# CLKB_clocking_system.net
KiCad netlist of a schematic drawn in Altium Designer
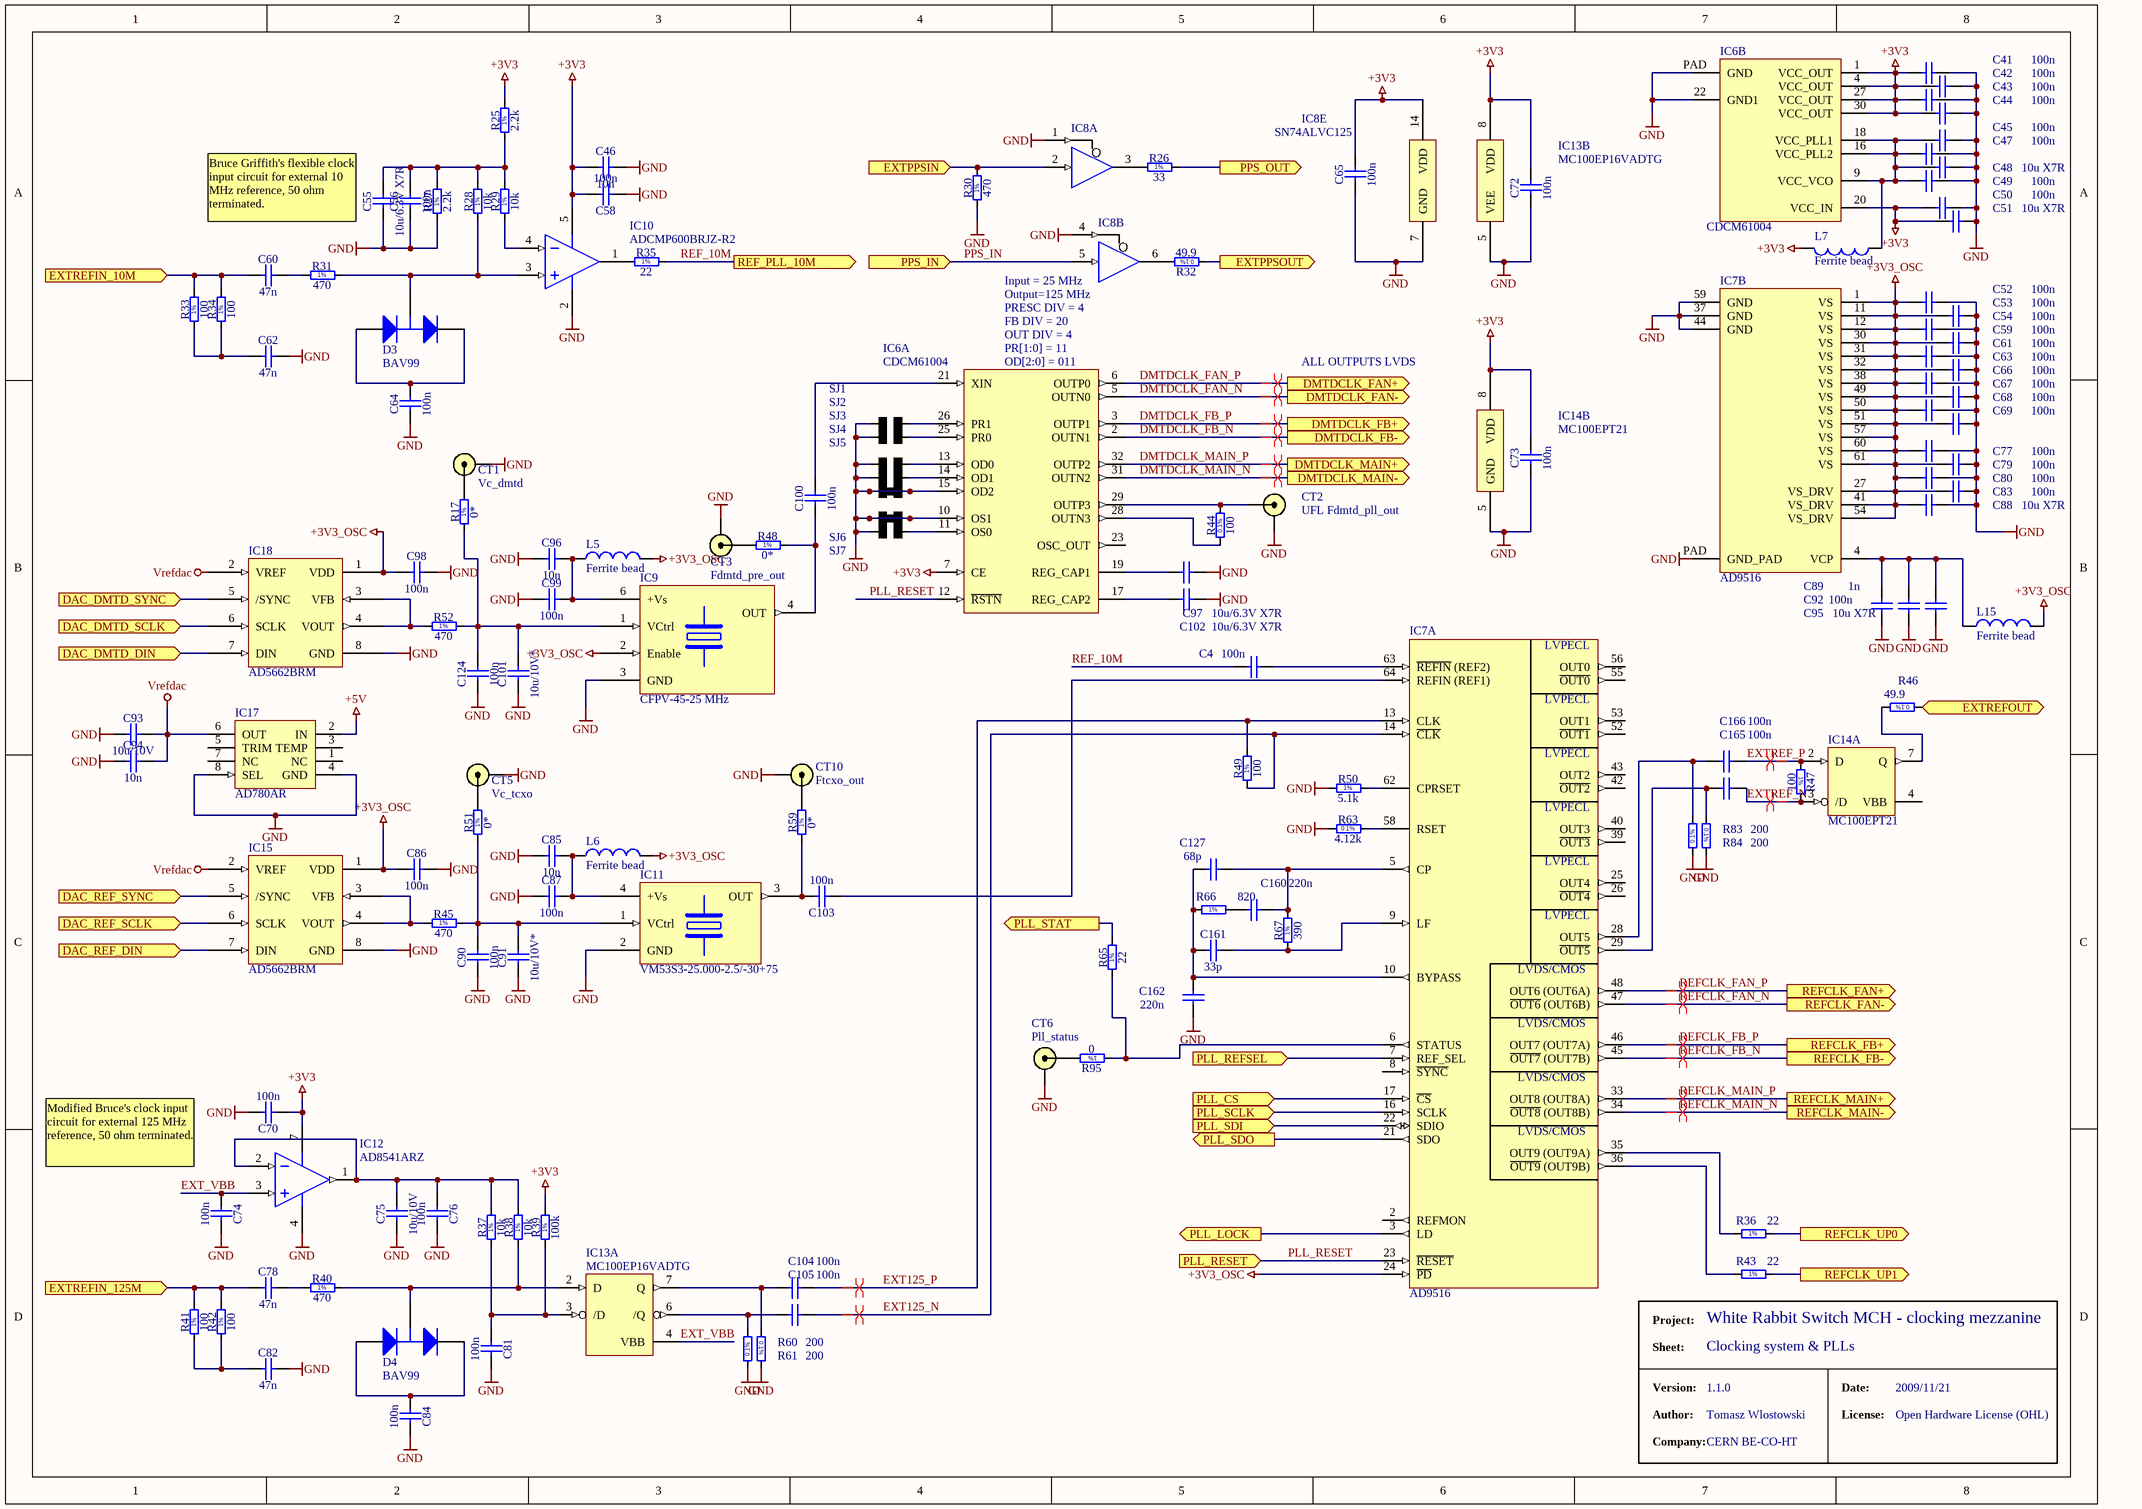
[diagram p0: CLKB_clocking_system.SchDoc]

(export (version "E")
  (design (tool "Eeschema 10.0.6"))
  (components
    (comp (ref "C4")
      (value "100n")
      (footprint "CAPC1608X87N")
      (description "Non-polarised capacitor")
      (fields
        (field (name "PART NUMBER") "CC0603_100NF_50V_10%_X7R")
        (field (name "VOLTAGE") "50V")
        (field (name "AUTHOR") "CERN DEM JLC")
      )
      (libsource (lib "Capacitors") (part "Capacitor - non polarized"))
    )
    (comp (ref "C41")
      (value "100n")
      (footprint "CAPC1005X55N")
      (description "Non-polarised capacitor")
      (fields
        (field (name "PART NUMBER") "CC0402_100NF_16V_10%_X7R")
        (field (name "VOLTAGE") "16V")
        (field (name "AUTHOR") "CERN DEM JLC")
      )
      (libsource (lib "Capacitors") (part "Capacitor - non polarized"))
    )
    (comp (ref "C42")
      (value "100n")
      (footprint "CAPC1005X55N")
      (description "Non-polarised capacitor")
      (fields
        (field (name "PART NUMBER") "CC0402_100NF_16V_10%_X7R")
        (field (name "VOLTAGE") "16V")
        (field (name "AUTHOR") "CERN DEM JLC")
      )
      (libsource (lib "Capacitors") (part "Capacitor - non polarized"))
    )
    (comp (ref "C43")
      (value "100n")
      (footprint "CAPC1005X55N")
      (description "Non-polarised capacitor")
      (fields
        (field (name "PART NUMBER") "CC0402_100NF_16V_10%_X7R")
        (field (name "VOLTAGE") "16V")
        (field (name "AUTHOR") "CERN DEM JLC")
      )
      (libsource (lib "Capacitors") (part "Capacitor - non polarized"))
    )
    (comp (ref "C44")
      (value "100n")
      (footprint "CAPC1005X55N")
      (description "Non-polarised capacitor")
      (fields
        (field (name "PART NUMBER") "CC0402_100NF_16V_10%_X7R")
        (field (name "VOLTAGE") "16V")
        (field (name "AUTHOR") "CERN DEM JLC")
      )
      (libsource (lib "Capacitors") (part "Capacitor - non polarized"))
    )
    (comp (ref "C45")
      (value "100n")
      (footprint "CAPC1005X55N")
      (description "Non-polarised capacitor")
      (fields
        (field (name "PART NUMBER") "CC0402_100NF_16V_10%_X7R")
        (field (name "VOLTAGE") "16V")
        (field (name "AUTHOR") "CERN DEM JLC")
      )
      (libsource (lib "Capacitors") (part "Capacitor - non polarized"))
    )
    (comp (ref "C46")
      (value "10n")
      (footprint "CAPC1608X87N")
      (description "Non-polarised capacitor")
      (fields
        (field (name "PART NUMBER") "CC0603_10NF_50V_10%_X7R")
        (field (name "VOLTAGE") "50V")
        (field (name "AUTHOR") "CERN DEM JLC")
      )
      (libsource (lib "Capacitors") (part "Capacitor - non polarized"))
    )
    (comp (ref "C47")
      (value "100n")
      (footprint "CAPC1005X55N")
      (description "Non-polarised capacitor")
      (fields
        (field (name "PART NUMBER") "CC0402_100NF_16V_10%_X7R")
        (field (name "VOLTAGE") "16V")
        (field (name "AUTHOR") "CERN DEM JLC")
      )
      (libsource (lib "Capacitors") (part "Capacitor - non polarized"))
    )
    (comp (ref "C48")
      (value "10u X7R")
      (footprint "CAPC1608X87N")
      (description "Non-polarised capacitor")
      (fields
        (field (name "PART NUMBER") "CC0603_10UF_6.3V_20%_X5R")
        (field (name "VOLTAGE") "6.3V")
        (field (name "AUTHOR") "CERN DEM JLC")
      )
      (libsource (lib "Capacitors") (part "Capacitor - non polarized"))
    )
    (comp (ref "C49")
      (value "100n")
      (footprint "CAPC1005X55N")
      (description "Non-polarised capacitor")
      (fields
        (field (name "PART NUMBER") "CC0402_100NF_16V_10%_X7R")
        (field (name "VOLTAGE") "16V")
        (field (name "AUTHOR") "CERN DEM JLC")
      )
      (libsource (lib "Capacitors") (part "Capacitor - non polarized"))
    )
    (comp (ref "C50")
      (value "100n")
      (footprint "CAPC1005X55N")
      (description "Non-polarised capacitor")
      (fields
        (field (name "PART NUMBER") "CC0402_100NF_16V_10%_X7R")
        (field (name "VOLTAGE") "16V")
        (field (name "AUTHOR") "CERN DEM JLC")
      )
      (libsource (lib "Capacitors") (part "Capacitor - non polarized"))
    )
    (comp (ref "C51")
      (value "10u X7R")
      (footprint "CAPC1608X87N")
      (description "Non-polarised capacitor")
      (fields
        (field (name "PART NUMBER") "CC0603_10UF_6.3V_20%_X5R")
        (field (name "VOLTAGE") "6.3V")
        (field (name "AUTHOR") "CERN DEM JLC")
      )
      (libsource (lib "Capacitors") (part "Capacitor - non polarized"))
    )
    (comp (ref "C52")
      (value "100n")
      (footprint "CAPC1005X55N")
      (description "Non-polarised capacitor")
      (fields
        (field (name "PART NUMBER") "CC0402_100NF_16V_10%_X7R")
        (field (name "VOLTAGE") "16V")
        (field (name "AUTHOR") "CERN DEM JLC")
      )
      (libsource (lib "Capacitors") (part "Capacitor - non polarized"))
    )
    (comp (ref "C53")
      (value "100n")
      (footprint "CAPC1005X55N")
      (description "Non-polarised capacitor")
      (fields
        (field (name "PART NUMBER") "CC0402_100NF_16V_10%_X7R")
        (field (name "VOLTAGE") "16V")
        (field (name "AUTHOR") "CERN DEM JLC")
      )
      (libsource (lib "Capacitors") (part "Capacitor - non polarized"))
    )
    (comp (ref "C54")
      (value "100n")
      (footprint "CAPC1005X55N")
      (description "Non-polarised capacitor")
      (fields
        (field (name "PART NUMBER") "CC0402_100NF_16V_10%_X7R")
        (field (name "VOLTAGE") "16V")
        (field (name "AUTHOR") "CERN DEM JLC")
      )
      (libsource (lib "Capacitors") (part "Capacitor - non polarized"))
    )
    (comp (ref "C55")
      (value "10u/6.3V X7R")
      (footprint "CAPC3216X140N")
      (description "Non-polarised capacitor")
      (fields
        (field (name "PART NUMBER") "CC1206_10UF_10V_10%_X7R")
        (field (name "VOLTAGE") "10V")
        (field (name "AUTHOR") "CERN DEM JLC")
      )
      (libsource (lib "Capacitors") (part "Capacitor - non polarized"))
    )
    (comp (ref "C56")
      (value "100n")
      (footprint "CAPC1608X87N")
      (description "Non-polarised capacitor")
      (fields
        (field (name "PART NUMBER") "CC0603_100NF_50V_10%_X7R")
        (field (name "VOLTAGE") "50V")
        (field (name "AUTHOR") "CERN DEM JLC")
      )
      (libsource (lib "Capacitors") (part "Capacitor - non polarized"))
    )
    (comp (ref "C58")
      (value "100n")
      (footprint "CAPC1608X87N")
      (description "Non-polarised capacitor")
      (fields
        (field (name "PART NUMBER") "CC0603_100NF_50V_10%_X7R")
        (field (name "VOLTAGE") "50V")
        (field (name "AUTHOR") "CERN DEM JLC")
      )
      (libsource (lib "Capacitors") (part "Capacitor - non polarized"))
    )
    (comp (ref "C59")
      (value "100n")
      (footprint "CAPC1005X55N")
      (description "Non-polarised capacitor")
      (fields
        (field (name "PART NUMBER") "CC0402_100NF_16V_10%_X7R")
        (field (name "VOLTAGE") "16V")
        (field (name "AUTHOR") "CERN DEM JLC")
      )
      (libsource (lib "Capacitors") (part "Capacitor - non polarized"))
    )
    (comp (ref "C60")
      (value "47n")
      (footprint "CAPC1608X87N")
      (description "Non-polarised capacitor")
      (fields
        (field (name "PART NUMBER") "CC0603_47NF_25V_10%_X7R")
        (field (name "VOLTAGE") "25V")
        (field (name "AUTHOR") "CERN DEM JLC")
      )
      (libsource (lib "Capacitors") (part "Capacitor - non polarized"))
    )
    (comp (ref "C61")
      (value "100n")
      (footprint "CAPC1005X55N")
      (description "Non-polarised capacitor")
      (fields
        (field (name "PART NUMBER") "CC0402_100NF_16V_10%_X7R")
        (field (name "VOLTAGE") "16V")
        (field (name "AUTHOR") "CERN DEM JLC")
      )
      (libsource (lib "Capacitors") (part "Capacitor - non polarized"))
    )
    (comp (ref "C62")
      (value "47n")
      (footprint "CAPC1608X87N")
      (description "Non-polarised capacitor")
      (fields
        (field (name "PART NUMBER") "CC0603_47NF_25V_10%_X7R")
        (field (name "VOLTAGE") "25V")
        (field (name "AUTHOR") "CERN DEM JLC")
      )
      (libsource (lib "Capacitors") (part "Capacitor - non polarized"))
    )
    (comp (ref "C63")
      (value "100n")
      (footprint "CAPC1005X55N")
      (description "Non-polarised capacitor")
      (fields
        (field (name "PART NUMBER") "CC0402_100NF_16V_10%_X7R")
        (field (name "VOLTAGE") "16V")
        (field (name "AUTHOR") "CERN DEM JLC")
      )
      (libsource (lib "Capacitors") (part "Capacitor - non polarized"))
    )
    (comp (ref "C64")
      (value "100n")
      (footprint "CAPC1608X87N")
      (description "Non-polarised capacitor")
      (fields
        (field (name "PART NUMBER") "CC0603_100NF_50V_10%_X7R")
        (field (name "VOLTAGE") "50V")
        (field (name "AUTHOR") "CERN DEM JLC")
      )
      (libsource (lib "Capacitors") (part "Capacitor - non polarized"))
    )
    (comp (ref "C65")
      (value "100n")
      (footprint "CAPC1608X87N")
      (description "Non-polarised capacitor")
      (fields
        (field (name "PART NUMBER") "CC0603_100NF_50V_10%_X7R")
        (field (name "VOLTAGE") "50V")
        (field (name "AUTHOR") "CERN DEM JLC")
      )
      (libsource (lib "Capacitors") (part "Capacitor - non polarized"))
    )
    (comp (ref "C66")
      (value "100n")
      (footprint "CAPC1005X55N")
      (description "Non-polarised capacitor")
      (fields
        (field (name "PART NUMBER") "CC0402_100NF_16V_10%_X7R")
        (field (name "VOLTAGE") "16V")
        (field (name "AUTHOR") "CERN DEM JLC")
      )
      (libsource (lib "Capacitors") (part "Capacitor - non polarized"))
    )
    (comp (ref "C67")
      (value "100n")
      (footprint "CAPC1005X55N")
      (description "Non-polarised capacitor")
      (fields
        (field (name "PART NUMBER") "CC0402_100NF_16V_10%_X7R")
        (field (name "VOLTAGE") "16V")
        (field (name "AUTHOR") "CERN DEM JLC")
      )
      (libsource (lib "Capacitors") (part "Capacitor - non polarized"))
    )
    (comp (ref "C68")
      (value "100n")
      (footprint "CAPC1005X55N")
      (description "Non-polarised capacitor")
      (fields
        (field (name "PART NUMBER") "CC0402_100NF_16V_10%_X7R")
        (field (name "VOLTAGE") "16V")
        (field (name "AUTHOR") "CERN DEM JLC")
      )
      (libsource (lib "Capacitors") (part "Capacitor - non polarized"))
    )
    (comp (ref "C69")
      (value "100n")
      (footprint "CAPC1005X55N")
      (description "Non-polarised capacitor")
      (fields
        (field (name "PART NUMBER") "CC0402_100NF_16V_10%_X7R")
        (field (name "VOLTAGE") "16V")
        (field (name "AUTHOR") "CERN DEM JLC")
      )
      (libsource (lib "Capacitors") (part "Capacitor - non polarized"))
    )
    (comp (ref "C70")
      (value "100n")
      (footprint "CAPC1608X87N")
      (description "Non-polarised capacitor")
      (fields
        (field (name "PART NUMBER") "CC0603_100NF_50V_10%_X7R")
        (field (name "VOLTAGE") "50V")
        (field (name "AUTHOR") "CERN DEM JLC")
      )
      (libsource (lib "Capacitors") (part "Capacitor - non polarized"))
    )
    (comp (ref "C72")
      (value "100n")
      (footprint "CAPC1608X87N")
      (description "Non-polarised capacitor")
      (fields
        (field (name "PART NUMBER") "CC0603_100NF_50V_10%_X7R")
        (field (name "VOLTAGE") "50V")
        (field (name "AUTHOR") "CERN DEM JLC")
      )
      (libsource (lib "Capacitors") (part "Capacitor - non polarized"))
    )
    (comp (ref "C73")
      (value "100n")
      (footprint "CAPC1608X87N")
      (description "Non-polarised capacitor")
      (fields
        (field (name "PART NUMBER") "CC0603_100NF_50V_10%_X7R")
        (field (name "VOLTAGE") "50V")
        (field (name "AUTHOR") "CERN DEM JLC")
      )
      (libsource (lib "Capacitors") (part "Capacitor - non polarized"))
    )
    (comp (ref "C74")
      (value "100n")
      (footprint "CAPC1608X87N")
      (description "Non-polarised capacitor")
      (fields
        (field (name "PART NUMBER") "CC0603_100NF_50V_10%_X7R")
        (field (name "VOLTAGE") "50V")
        (field (name "AUTHOR") "CERN DEM JLC")
      )
      (libsource (lib "Capacitors") (part "Capacitor - non polarized"))
    )
    (comp (ref "C75")
      (value "10u/10V")
      (footprint "CAPC3216X140N")
      (description "Non-polarised capacitor")
      (fields
        (field (name "PART NUMBER") "CC1206_10UF_10V_10%_X7R")
        (field (name "VOLTAGE") "10V")
        (field (name "AUTHOR") "CERN DEM JLC")
      )
      (libsource (lib "Capacitors") (part "Capacitor - non polarized"))
    )
    (comp (ref "C76")
      (value "100n")
      (footprint "CAPC1608X87N")
      (description "Non-polarised capacitor")
      (fields
        (field (name "PART NUMBER") "CC0603_100NF_50V_10%_X7R")
        (field (name "VOLTAGE") "50V")
        (field (name "AUTHOR") "CERN DEM JLC")
      )
      (libsource (lib "Capacitors") (part "Capacitor - non polarized"))
    )
    (comp (ref "C77")
      (value "100n")
      (footprint "CAPC1005X55N")
      (description "Non-polarised capacitor")
      (fields
        (field (name "PART NUMBER") "CC0402_100NF_16V_10%_X7R")
        (field (name "VOLTAGE") "16V")
        (field (name "AUTHOR") "CERN DEM JLC")
      )
      (libsource (lib "Capacitors") (part "Capacitor - non polarized"))
    )
    (comp (ref "C78")
      (value "47n")
      (footprint "CAPC1608X87N")
      (description "Non-polarised capacitor")
      (fields
        (field (name "PART NUMBER") "CC0603_47NF_25V_10%_X7R")
        (field (name "VOLTAGE") "25V")
        (field (name "AUTHOR") "CERN DEM JLC")
      )
      (libsource (lib "Capacitors") (part "Capacitor - non polarized"))
    )
    (comp (ref "C79")
      (value "100n")
      (footprint "CAPC1005X55N")
      (description "Non-polarised capacitor")
      (fields
        (field (name "PART NUMBER") "CC0402_100NF_16V_10%_X7R")
        (field (name "VOLTAGE") "16V")
        (field (name "AUTHOR") "CERN DEM JLC")
      )
      (libsource (lib "Capacitors") (part "Capacitor - non polarized"))
    )
    (comp (ref "C80")
      (value "100n")
      (footprint "CAPC1005X55N")
      (description "Non-polarised capacitor")
      (fields
        (field (name "PART NUMBER") "CC0402_100NF_16V_10%_X7R")
        (field (name "VOLTAGE") "16V")
        (field (name "AUTHOR") "CERN DEM JLC")
      )
      (libsource (lib "Capacitors") (part "Capacitor - non polarized"))
    )
    (comp (ref "C81")
      (value "100n")
      (footprint "CAPC1608X87N")
      (description "Non-polarised capacitor")
      (fields
        (field (name "PART NUMBER") "CC0603_100NF_50V_10%_X7R")
        (field (name "VOLTAGE") "50V")
        (field (name "AUTHOR") "CERN DEM JLC")
      )
      (libsource (lib "Capacitors") (part "Capacitor - non polarized"))
    )
    (comp (ref "C82")
      (value "47n")
      (footprint "CAPC1608X87N")
      (description "Non-polarised capacitor")
      (fields
        (field (name "PART NUMBER") "CC0603_47NF_25V_10%_X7R")
        (field (name "VOLTAGE") "25V")
        (field (name "AUTHOR") "CERN DEM JLC")
      )
      (libsource (lib "Capacitors") (part "Capacitor - non polarized"))
    )
    (comp (ref "C83")
      (value "100n")
      (footprint "CAPC1005X55N")
      (description "Non-polarised capacitor")
      (fields
        (field (name "PART NUMBER") "CC0402_100NF_16V_10%_X7R")
        (field (name "VOLTAGE") "16V")
        (field (name "AUTHOR") "CERN DEM JLC")
      )
      (libsource (lib "Capacitors") (part "Capacitor - non polarized"))
    )
    (comp (ref "C84")
      (value "100n")
      (footprint "CAPC1608X87N")
      (description "Non-polarised capacitor")
      (fields
        (field (name "PART NUMBER") "CC0603_100NF_50V_10%_X7R")
        (field (name "VOLTAGE") "50V")
        (field (name "AUTHOR") "CERN DEM JLC")
      )
      (libsource (lib "Capacitors") (part "Capacitor - non polarized"))
    )
    (comp (ref "C85")
      (value "10n")
      (footprint "CAPC1608X87N")
      (description "Non-polarised capacitor")
      (fields
        (field (name "PART NUMBER") "CC0603_10NF_50V_10%_X7R")
        (field (name "VOLTAGE") "50V")
        (field (name "AUTHOR") "CERN DEM JLC")
      )
      (libsource (lib "Capacitors") (part "Capacitor - non polarized"))
    )
    (comp (ref "C86")
      (value "100n")
      (footprint "CAPC1608X87N")
      (description "Non-polarised capacitor")
      (fields
        (field (name "PART NUMBER") "CC0603_100NF_50V_10%_X7R")
        (field (name "VOLTAGE") "50V")
        (field (name "AUTHOR") "CERN DEM JLC")
      )
      (libsource (lib "Capacitors") (part "Capacitor - non polarized"))
    )
    (comp (ref "C87")
      (value "100n")
      (footprint "CAPC1608X87N")
      (description "Non-polarised capacitor")
      (fields
        (field (name "PART NUMBER") "CC0603_100NF_50V_10%_X7R")
        (field (name "VOLTAGE") "50V")
        (field (name "AUTHOR") "CERN DEM JLC")
      )
      (libsource (lib "Capacitors") (part "Capacitor - non polarized"))
    )
    (comp (ref "C88")
      (value "10u X7R")
      (footprint "CAPC1608X87N")
      (description "Non-polarised capacitor")
      (fields
        (field (name "PART NUMBER") "CC0603_10UF_6.3V_20%_X5R")
        (field (name "VOLTAGE") "6.3V")
        (field (name "AUTHOR") "CERN DEM JLC")
      )
      (libsource (lib "Capacitors") (part "Capacitor - non polarized"))
    )
    (comp (ref "C89")
      (value "1n")
      (footprint "CAPC1005X55N")
      (description "Non-polarised capacitor")
      (fields
        (field (name "PART NUMBER") "CC0402_1NF_50V_10%_X7R")
        (field (name "VOLTAGE") "50V")
        (field (name "AUTHOR") "CERN DEM JLC")
      )
      (libsource (lib "Capacitors") (part "Capacitor - non polarized"))
    )
    (comp (ref "C90")
      (value "100n")
      (footprint "CAPC1608X87N")
      (description "Non-polarised capacitor")
      (fields
        (field (name "PART NUMBER") "CC0603_100NF_50V_10%_X7R")
        (field (name "VOLTAGE") "50V")
        (field (name "AUTHOR") "CERN DEM JLC")
      )
      (libsource (lib "Capacitors") (part "Capacitor - non polarized"))
    )
    (comp (ref "C91")
      (value "10u/10V*")
      (footprint "CAPC3216X140N")
      (description "Non-polarised capacitor")
      (fields
        (field (name "PART NUMBER") "CC1206_10UF_10V_10%_X7R")
        (field (name "VOLTAGE") "10V")
        (field (name "AUTHOR") "CERN DEM JLC")
      )
      (libsource (lib "Capacitors") (part "Capacitor - non polarized"))
    )
    (comp (ref "C92")
      (value "100n")
      (footprint "CAPC1005X55N")
      (description "Non-polarised capacitor")
      (fields
        (field (name "PART NUMBER") "CC0402_100NF_16V_10%_X7R")
        (field (name "VOLTAGE") "16V")
        (field (name "AUTHOR") "CERN DEM JLC")
      )
      (libsource (lib "Capacitors") (part "Capacitor - non polarized"))
    )
    (comp (ref "C93")
      (value "10u/10V")
      (footprint "CAPC3216X140N")
      (description "Non-polarised capacitor")
      (fields
        (field (name "PART NUMBER") "CC1206_10UF_10V_10%_X7R")
        (field (name "VOLTAGE") "10V")
        (field (name "AUTHOR") "CERN DEM JLC")
      )
      (libsource (lib "Capacitors") (part "Capacitor - non polarized"))
    )
    (comp (ref "C94")
      (value "10n")
      (footprint "CAPC1608X87N")
      (description "Non-polarised capacitor")
      (fields
        (field (name "PART NUMBER") "CC0603_10NF_50V_10%_X7R")
        (field (name "VOLTAGE") "50V")
        (field (name "AUTHOR") "CERN DEM JLC")
      )
      (libsource (lib "Capacitors") (part "Capacitor - non polarized"))
    )
    (comp (ref "C95")
      (value "10u X7R")
      (footprint "CAPC1608X87N")
      (description "Non-polarised capacitor")
      (fields
        (field (name "PART NUMBER") "CC0603_10UF_6.3V_20%_X5R")
        (field (name "VOLTAGE") "6.3V")
        (field (name "AUTHOR") "CERN DEM JLC")
      )
      (libsource (lib "Capacitors") (part "Capacitor - non polarized"))
    )
    (comp (ref "C96")
      (value "10n")
      (footprint "CAPC1608X87N")
      (description "Non-polarised capacitor")
      (fields
        (field (name "PART NUMBER") "CC0603_10NF_50V_10%_X7R")
        (field (name "VOLTAGE") "50V")
        (field (name "AUTHOR") "CERN DEM JLC")
      )
      (libsource (lib "Capacitors") (part "Capacitor - non polarized"))
    )
    (comp (ref "C97")
      (value "10u/6.3V X7R")
      (footprint "CAPC1608X87N")
      (description "Non-polarised capacitor")
      (fields
        (field (name "PART NUMBER") "CC0603_10UF_6.3V_20%_X5R")
        (field (name "VOLTAGE") "6.3V")
        (field (name "AUTHOR") "CERN DEM JLC")
      )
      (libsource (lib "Capacitors") (part "Capacitor - non polarized"))
    )
    (comp (ref "C98")
      (value "100n")
      (footprint "CAPC1608X87N")
      (description "Non-polarised capacitor")
      (fields
        (field (name "PART NUMBER") "CC0603_100NF_50V_10%_X7R")
        (field (name "VOLTAGE") "50V")
        (field (name "AUTHOR") "CERN DEM JLC")
      )
      (libsource (lib "Capacitors") (part "Capacitor - non polarized"))
    )
    (comp (ref "C99")
      (value "100n")
      (footprint "CAPC1608X87N")
      (description "Non-polarised capacitor")
      (fields
        (field (name "PART NUMBER") "CC0603_100NF_50V_10%_X7R")
        (field (name "VOLTAGE") "50V")
        (field (name "AUTHOR") "CERN DEM JLC")
      )
      (libsource (lib "Capacitors") (part "Capacitor - non polarized"))
    )
    (comp (ref "C100")
      (value "100n")
      (footprint "CAPC1608X87N")
      (description "Non-polarised capacitor")
      (fields
        (field (name "PART NUMBER") "CC0603_100NF_50V_10%_X7R")
        (field (name "VOLTAGE") "50V")
        (field (name "AUTHOR") "CERN DEM JLC")
      )
      (libsource (lib "Capacitors") (part "Capacitor - non polarized"))
    )
    (comp (ref "C101")
      (value "10u/10V*")
      (footprint "CAPC3216X140N")
      (description "Non-polarised capacitor")
      (fields
        (field (name "PART NUMBER") "CC1206_10UF_10V_10%_X7R")
        (field (name "VOLTAGE") "10V")
        (field (name "AUTHOR") "CERN DEM JLC")
      )
      (libsource (lib "Capacitors") (part "Capacitor - non polarized"))
    )
    (comp (ref "C102")
      (value "10u/6.3V X7R")
      (footprint "CAPC1608X87N")
      (description "Non-polarised capacitor")
      (fields
        (field (name "PART NUMBER") "CC0603_10UF_6.3V_20%_X5R")
        (field (name "VOLTAGE") "6.3V")
        (field (name "AUTHOR") "CERN DEM JLC")
      )
      (libsource (lib "Capacitors") (part "Capacitor - non polarized"))
    )
    (comp (ref "C103")
      (value "100n")
      (footprint "CAPC1608X87N")
      (description "Non-polarised capacitor")
      (fields
        (field (name "PART NUMBER") "CC0603_100NF_50V_10%_X7R")
        (field (name "VOLTAGE") "50V")
        (field (name "AUTHOR") "CERN DEM JLC")
      )
      (libsource (lib "Capacitors") (part "Capacitor - non polarized"))
    )
    (comp (ref "C104")
      (value "100n")
      (footprint "CAPC1005X55N")
      (description "Non-polarised capacitor")
      (fields
        (field (name "PART NUMBER") "CC0402_100NF_16V_10%_X7R")
        (field (name "VOLTAGE") "16V")
        (field (name "AUTHOR") "CERN DEM JLC")
      )
      (libsource (lib "Capacitors") (part "Capacitor - non polarized"))
    )
    (comp (ref "C105")
      (value "100n")
      (footprint "CAPC1005X55N")
      (description "Non-polarised capacitor")
      (fields
        (field (name "PART NUMBER") "CC0402_100NF_16V_10%_X7R")
        (field (name "VOLTAGE") "16V")
        (field (name "AUTHOR") "CERN DEM JLC")
      )
      (libsource (lib "Capacitors") (part "Capacitor - non polarized"))
    )
    (comp (ref "C124")
      (value "100n")
      (footprint "CAPC1608X87N")
      (description "Non-polarised capacitor")
      (fields
        (field (name "PART NUMBER") "CC0603_100NF_50V_10%_X7R")
        (field (name "VOLTAGE") "50V")
        (field (name "AUTHOR") "CERN DEM JLC")
      )
      (libsource (lib "Capacitors") (part "Capacitor - non polarized"))
    )
    (comp (ref "C127")
      (value "68p")
      (footprint "CAPC1608X87N")
      (description "Non-polarised capacitor")
      (fields
        (field (name "PART NUMBER") "CC0603_68PF_50V_5%_NP0")
        (field (name "VOLTAGE") "50V")
        (field (name "AUTHOR") "CERN DEM JLC")
      )
      (libsource (lib "Capacitors") (part "Capacitor - non polarized"))
    )
    (comp (ref "C160")
      (value "220n")
      (footprint "CAPC1608X87N")
      (description "Non-polarised capacitor")
      (fields
        (field (name "PART NUMBER") "CC0603_220NF_16V_+80%-20%_Y5V")
        (field (name "VOLTAGE") "16V")
        (field (name "AUTHOR") "CERN DEM JLC")
      )
      (libsource (lib "Capacitors") (part "Capacitor - non polarized"))
    )
    (comp (ref "C161")
      (value "33p")
      (footprint "CAPC1608X87N")
      (description "Non-polarised capacitor")
      (fields
        (field (name "PART NUMBER") "CC0603_33PF_50V_5%_NP0")
        (field (name "VOLTAGE") "50V")
        (field (name "AUTHOR") "CERN DEM JLC")
      )
      (libsource (lib "Capacitors") (part "Capacitor - non polarized"))
    )
    (comp (ref "C162")
      (value "220n")
      (footprint "CAPC1608X87N")
      (description "Non-polarised capacitor")
      (fields
        (field (name "PART NUMBER") "CC0603_220NF_16V_+80%-20%_Y5V")
        (field (name "VOLTAGE") "16V")
        (field (name "AUTHOR") "CERN DEM JLC")
      )
      (libsource (lib "Capacitors") (part "Capacitor - non polarized"))
    )
    (comp (ref "C165")
      (value "100n")
      (footprint "CAPC1005X55N")
      (description "Non-polarised capacitor")
      (fields
        (field (name "PART NUMBER") "CC0402_100NF_16V_10%_X7R")
        (field (name "VOLTAGE") "16V")
        (field (name "AUTHOR") "CERN DEM JLC")
      )
      (libsource (lib "Capacitors") (part "Capacitor - non polarized"))
    )
    (comp (ref "C166")
      (value "100n")
      (footprint "CAPC1005X55N")
      (description "Non-polarised capacitor")
      (fields
        (field (name "PART NUMBER") "CC0402_100NF_16V_10%_X7R")
        (field (name "VOLTAGE") "16V")
        (field (name "AUTHOR") "CERN DEM JLC")
      )
      (libsource (lib "Capacitors") (part "Capacitor - non polarized"))
    )
    (comp (ref "CT1")
      (value "Vc_dmtd")
      (footprint "CON_UFL_HIROSE_RECEPTACLE")
      (description "UFL connector testpoint")
      (libsource (lib "wr_switch") (part "CON_TESTPOINT_UFL"))
    )
    (comp (ref "CT2")
      (value "UFL Fdmtd_pll_out")
      (footprint "CON_UFL_HIROSE_RECEPTACLE")
      (description "UFL connector testpoint")
      (libsource (lib "") (part "CON_TESTPOINT_UFL_1"))
    )
    (comp (ref "CT3")
      (value "Fdmtd_pre_out")
      (footprint "CON_UFL_HIROSE_RECEPTACLE")
      (description "UFL connector testpoint")
      (libsource (lib "") (part "CON_TESTPOINT_UFL_1"))
    )
    (comp (ref "CT5")
      (value "Vc_tcxo")
      (footprint "CON_UFL_HIROSE_RECEPTACLE")
      (description "UFL connector testpoint")
      (libsource (lib "wr_switch") (part "CON_TESTPOINT_UFL"))
    )
    (comp (ref "CT6")
      (value "Pll_status")
      (footprint "CON_UFL_HIROSE_RECEPTACLE")
      (description "UFL connector testpoint")
      (libsource (lib "") (part "CON_TESTPOINT_UFL_1"))
    )
    (comp (ref "CT10")
      (value "Ftcxo_out")
      (footprint "CON_UFL_HIROSE_RECEPTACLE")
      (description "UFL connector testpoint")
      (libsource (lib "") (part "CON_TESTPOINT_UFL_1"))
    )
    (comp (ref "D3")
      (value "BAV99")
      (footprint "SOT-23")
      (description "Silicon Switching Diode Array for High-Speed Switching")
      (fields (field (name "PUBLISHER") "Altium Limited"))
      (libsource (lib "Infineon Discrete Diode") (part "BAV99"))
    )
    (comp (ref "D4")
      (value "BAV99")
      (footprint "SOT-23")
      (description "Silicon Switching Diode Array for High-Speed Switching")
      (fields (field (name "PUBLISHER") "Altium Limited"))
      (libsource (lib "Infineon Discrete Diode") (part "BAV99"))
    )
    (comp (ref "IC6")
      (value "CDCM61004")
      (footprint "QFN32_POWERPAD")
      (description "PLL generator with 1:4 fanout")
      (libsource (lib "wr_switch") (part "CDCM61004"))
    )
    (comp (ref "IC7")
      (value "AD9516")
      (footprint "QFN50P900X900X100-64M")
      (description "PLL with clock fanout")
      (libsource (lib "wr_switch") (part "AD9516"))
    )
    (comp (ref "IC8")
      (value "SN74ALVC125")
      (footprint "SO-14")
      (description "Quad Buffer with 3-State Outputs with TTL Compatible Inputs")
      (libsource (lib "wr_switch") (part "SN74ALVC125"))
    )
    (comp (ref "IC9")
      (value "CFPV-45-25 MHz")
      (footprint "vs-705")
      (description "VCXO oscillator")
      (libsource (lib "wr_switch") (part "VCXO_CFPV_45"))
    )
    (comp (ref "IC10")
      (value "ADCMP600BRJZ-R2")
      (footprint "SOT23-5AL")
      (description "Analog Devices fast comparator")
      (fields (field (name "Comment") "ADCMP600"))
      (libsource (lib "wr_switch") (part "ADCMP600"))
    )
    (comp (ref "IC11")
      (value "VM53S3-25.000-2.5/-30+75")
      (footprint "VCTCXO_VM53S")
      (description "VCTCXO oscillator")
      (libsource (lib "wr_switch") (part "VCTCXO_VM53S"))
    )
    (comp (ref "IC12")
      (value "AD8541ARZ")
      (footprint "SOIC127P600-8AL")
      (description "Analog Devices general purpose low-voltage R2R CMOS opamp")
      (fields (field (name "Comment") "AD8541"))
      (libsource (lib "wr_switch") (part "AD8541"))
    )
    (comp (ref "IC13")
      (value "MC100EP16VADTG")
      (footprint "TSOP65P490-8AN")
      (description "ONSemi differental receiver w/ECL output")
      (fields (field (name "Comment") "MC100EP16"))
      (libsource (lib "wr_switch") (part "MC100EP16"))
    )
    (comp (ref "IC14")
      (value "MC100EPT21")
      (footprint "TSOP65P490-8AN")
      (description "ONSemi LVDS/LVPECL -> LVTTL/LVCMOS buffer")
      (libsource (lib "wr_switch") (part "MC100EPT21"))
    )
    (comp (ref "IC15")
      (value "AD5662BRM")
      (footprint "TSOP65P490-8AN")
      (description "Analog Devices 16-bit DAC w/SPI interface, ext ref")
      (fields (field (name "Comment") "AD5662B"))
      (libsource (lib "wr_switch") (part "AD5662"))
    )
    (comp (ref "IC17")
      (value "AD780AR")
      (footprint "R-8C_M")
      (description "2.5V/3.0V High-Precision Reference")
      (fields (field (name "PUBLISHER") "Altium Limited"))
      (libsource (lib "AD Power Mgt Voltage Reference") (part "AD780AR"))
    )
    (comp (ref "IC18")
      (value "AD5662BRM")
      (footprint "TSOP65P490-8AN")
      (description "Analog Devices 16-bit DAC w/SPI interface, ext ref")
      (fields (field (name "Comment") "AD5662B"))
      (libsource (lib "wr_switch") (part "AD5662"))
    )
    (comp (ref "L5")
      (value "Ferrite bead")
      (footprint "INDC2012-0805")
      (fields (field (name "PUBLISHER") "Altium Limited"))
      (libsource (lib "Miscellaneous Devices") (part "Inductor"))
    )
    (comp (ref "L6")
      (value "Ferrite bead")
      (footprint "INDC2012-0805")
      (fields (field (name "PUBLISHER") "Altium Limited"))
      (libsource (lib "Miscellaneous Devices") (part "Inductor"))
    )
    (comp (ref "L7")
      (value "Ferrite bead")
      (footprint "INDC1608-0603")
      (fields (field (name "PUBLISHER") "Altium Limited"))
      (libsource (lib "Miscellaneous Devices") (part "Inductor"))
    )
    (comp (ref "L15")
      (value "Ferrite bead")
      (footprint "INDC1608-0603")
      (fields (field (name "PUBLISHER") "Altium Limited"))
      (libsource (lib "Miscellaneous Devices") (part "Inductor"))
    )
    (comp (ref "R17")
      (value "0*")
      (footprint "RESC1608X55N")
      (description "Resistor - 1%")
      (fields
        (field (name "PART NUMBER") "R0603_0R_JUMPER")
        (field (name "MANUFACTURER") "GENERIC")
        (field (name "AUTHOR") "CERN DEM JLC")
      )
      (libsource (lib "Resistors") (part "Resistor - 1%"))
    )
    (comp (ref "R25")
      (value "2.2k")
      (footprint "RESC1608X55N")
      (description "Resistor - 1%")
      (fields
        (field (name "PART NUMBER") "R0603_2K2_1%_0.1W_100PPM")
        (field (name "POWER") "0.1W")
        (field (name "AUTHOR") "CERN DEM JLC")
      )
      (libsource (lib "Resistors") (part "Resistor - 1%"))
    )
    (comp (ref "R26")
      (value "33")
      (footprint "RESC1608X55N")
      (description "Resistor - 1%")
      (fields
        (field (name "PART NUMBER") "R0603_33R_1%_0.1W_100PPM")
        (field (name "POWER") "0.1W")
        (field (name "AUTHOR") "CERN DEM JLC")
      )
      (libsource (lib "Resistors") (part "Resistor - 1%"))
    )
    (comp (ref "R27")
      (value "2.2k")
      (footprint "RESC1608X55N")
      (description "Resistor - 1%")
      (fields
        (field (name "PART NUMBER") "R0603_2K2_1%_0.1W_100PPM")
        (field (name "POWER") "0.1W")
        (field (name "AUTHOR") "CERN DEM JLC")
      )
      (libsource (lib "Resistors") (part "Resistor - 1%"))
    )
    (comp (ref "R28")
      (value "10k")
      (footprint "RESC1608X55N")
      (description "Resistor - 1%")
      (fields
        (field (name "PART NUMBER") "R0603_10K_1%_0.1W_100PPM")
        (field (name "POWER") "0.1W")
        (field (name "AUTHOR") "CERN DEM JLC")
      )
      (libsource (lib "Resistors") (part "Resistor - 1%"))
    )
    (comp (ref "R29")
      (value "10k")
      (footprint "RESC1608X55N")
      (description "Resistor - 1%")
      (fields
        (field (name "PART NUMBER") "R0603_10K_1%_0.1W_100PPM")
        (field (name "POWER") "0.1W")
        (field (name "AUTHOR") "CERN DEM JLC")
      )
      (libsource (lib "Resistors") (part "Resistor - 1%"))
    )
    (comp (ref "R30")
      (value "470")
      (footprint "RESC1608X55N")
      (description "Resistor - 1%")
      (fields
        (field (name "PART NUMBER") "R0603_470R_1%_0.1W_100PPM")
        (field (name "POWER") "0.1W")
        (field (name "AUTHOR") "CERN DEM JLC")
      )
      (libsource (lib "Resistors") (part "Resistor - 1%"))
    )
    (comp (ref "R31")
      (value "470")
      (footprint "RESC1608X55N")
      (description "Resistor - 1%")
      (fields
        (field (name "PART NUMBER") "R0603_470R_1%_0.1W_100PPM")
        (field (name "POWER") "0.1W")
        (field (name "AUTHOR") "CERN DEM JLC")
      )
      (libsource (lib "Resistors") (part "Resistor - 1%"))
    )
    (comp (ref "R32")
      (value "49.9")
      (footprint "RESC1608X55N")
      (description "Resistor - 0.1%")
      (fields
        (field (name "PART NUMBER") "R0603_49R9_0.1%_0.063W_10PPM")
        (field (name "POWER") "0.063W")
        (field (name "AUTHOR") "CERN DEM JLC")
      )
      (libsource (lib "Resistors") (part "Resistor - 0.1%"))
    )
    (comp (ref "R33")
      (value "100")
      (footprint "RESC1608X55N")
      (description "Resistor - 1%")
      (fields
        (field (name "PART NUMBER") "R0603_100R_1%_0.1W_100PPM")
        (field (name "POWER") "0.1W")
        (field (name "AUTHOR") "CERN DEM JLC")
      )
      (libsource (lib "Resistors") (part "Resistor - 1%"))
    )
    (comp (ref "R34")
      (value "100")
      (footprint "RESC1608X55N")
      (description "Resistor - 1%")
      (fields
        (field (name "PART NUMBER") "R0603_100R_1%_0.1W_100PPM")
        (field (name "POWER") "0.1W")
        (field (name "AUTHOR") "CERN DEM JLC")
      )
      (libsource (lib "Resistors") (part "Resistor - 1%"))
    )
    (comp (ref "R35")
      (value "22")
      (footprint "RESC1608X55N")
      (description "Resistor - 1%")
      (fields
        (field (name "PART NUMBER") "R0603_22R_1%_0.1W_100PPM")
        (field (name "POWER") "0.1W")
        (field (name "AUTHOR") "CERN DEM JLC")
      )
      (libsource (lib "Resistors") (part "Resistor - 1%"))
    )
    (comp (ref "R36")
      (value "22")
      (footprint "RESC1608X55N")
      (description "Resistor - 1%")
      (fields
        (field (name "PART NUMBER") "R0603_22R_1%_0.1W_100PPM")
        (field (name "POWER") "0.1W")
        (field (name "AUTHOR") "CERN DEM JLC")
      )
      (libsource (lib "Resistors") (part "Resistor - 1%"))
    )
    (comp (ref "R37")
      (value "10k")
      (footprint "RESC1608X55N")
      (description "Resistor - 1%")
      (fields
        (field (name "PART NUMBER") "R0603_10K_1%_0.1W_100PPM")
        (field (name "POWER") "0.1W")
        (field (name "AUTHOR") "CERN DEM JLC")
      )
      (libsource (lib "Resistors") (part "Resistor - 1%"))
    )
    (comp (ref "R38")
      (value "10k")
      (footprint "RESC1608X55N")
      (description "Resistor - 1%")
      (fields
        (field (name "PART NUMBER") "R0603_10K_1%_0.1W_100PPM")
        (field (name "POWER") "0.1W")
        (field (name "AUTHOR") "CERN DEM JLC")
      )
      (libsource (lib "Resistors") (part "Resistor - 1%"))
    )
    (comp (ref "R39")
      (value "100k")
      (footprint "RESC1608X55N")
      (description "Resistor - 1%")
      (fields
        (field (name "PART NUMBER") "R0603_100K_1%_0.1W_100PPM")
        (field (name "POWER") "0.1W")
        (field (name "AUTHOR") "CERN DEM JLC")
      )
      (libsource (lib "Resistors") (part "Resistor - 1%"))
    )
    (comp (ref "R40")
      (value "470")
      (footprint "RESC1608X55N")
      (description "Resistor - 1%")
      (fields
        (field (name "PART NUMBER") "R0603_470R_1%_0.1W_100PPM")
        (field (name "POWER") "0.1W")
        (field (name "AUTHOR") "CERN DEM JLC")
      )
      (libsource (lib "Resistors") (part "Resistor - 1%"))
    )
    (comp (ref "R41")
      (value "100")
      (footprint "RESC1608X55N")
      (description "Resistor - 1%")
      (fields
        (field (name "PART NUMBER") "R0603_100R_1%_0.1W_100PPM")
        (field (name "POWER") "0.1W")
        (field (name "AUTHOR") "CERN DEM JLC")
      )
      (libsource (lib "Resistors") (part "Resistor - 1%"))
    )
    (comp (ref "R42")
      (value "100")
      (footprint "RESC1608X55N")
      (description "Resistor - 1%")
      (fields
        (field (name "PART NUMBER") "R0603_100R_1%_0.1W_100PPM")
        (field (name "POWER") "0.1W")
        (field (name "AUTHOR") "CERN DEM JLC")
      )
      (libsource (lib "Resistors") (part "Resistor - 1%"))
    )
    (comp (ref "R43")
      (value "22")
      (footprint "RESC1608X55N")
      (description "Resistor - 1%")
      (fields
        (field (name "PART NUMBER") "R0603_22R_1%_0.1W_100PPM")
        (field (name "POWER") "0.1W")
        (field (name "AUTHOR") "CERN DEM JLC")
      )
      (libsource (lib "Resistors") (part "Resistor - 1%"))
    )
    (comp (ref "R44")
      (value "100")
      (footprint "RESC1608X55N")
      (description "Resistor - 0.1%")
      (fields
        (field (name "PART NUMBER") "R0603_100R_0.1%_0.063W_10PPM")
        (field (name "POWER") "0.063W")
        (field (name "AUTHOR") "CERN DEM JLC")
      )
      (libsource (lib "Resistors") (part "Resistor - 0.1%"))
    )
    (comp (ref "R45")
      (value "470")
      (footprint "RESC1608X55N")
      (description "Resistor - 1%")
      (fields
        (field (name "PART NUMBER") "R0603_470R_1%_0.1W_100PPM")
        (field (name "POWER") "0.1W")
        (field (name "AUTHOR") "CERN DEM JLC")
      )
      (libsource (lib "Resistors") (part "Resistor - 1%"))
    )
    (comp (ref "R46")
      (value "49.9")
      (footprint "RESC1608X55N")
      (description "Resistor - 0.1%")
      (fields
        (field (name "PART NUMBER") "R0603_49R9_0.1%_0.063W_10PPM")
        (field (name "POWER") "0.063W")
        (field (name "AUTHOR") "CERN DEM JLC")
      )
      (libsource (lib "Resistors") (part "Resistor - 0.1%"))
    )
    (comp (ref "R47")
      (value "100")
      (footprint "RESC1608X55N")
      (description "Resistor - 1%")
      (fields
        (field (name "PART NUMBER") "R0603_100R_1%_0.1W_100PPM")
        (field (name "POWER") "0.1W")
        (field (name "AUTHOR") "CERN DEM JLC")
      )
      (libsource (lib "Resistors") (part "Resistor - 1%"))
    )
    (comp (ref "R48")
      (value "0*")
      (footprint "RESC1608X55N")
      (description "Resistor - 1%")
      (fields
        (field (name "PART NUMBER") "R0603_0R_JUMPER")
        (field (name "MANUFACTURER") "GENERIC")
        (field (name "AUTHOR") "CERN DEM JLC")
      )
      (libsource (lib "Resistors") (part "Resistor - 1%"))
    )
    (comp (ref "R49")
      (value "100")
      (footprint "RESC1608X55N")
      (description "Resistor - 1%")
      (fields
        (field (name "PART NUMBER") "R0603_100R_1%_0.1W_100PPM")
        (field (name "POWER") "0.1W")
        (field (name "AUTHOR") "CERN DEM JLC")
      )
      (libsource (lib "Resistors") (part "Resistor - 1%"))
    )
    (comp (ref "R50")
      (value "5.1k")
      (footprint "RESC1608X55N")
      (description "Resistor - 1%")
      (fields
        (field (name "PART NUMBER") "R0603_5K1_1%_0.1W_100PPM")
        (field (name "POWER") "0.1W")
        (field (name "AUTHOR") "CERN DEM JLC")
      )
      (libsource (lib "Resistors") (part "Resistor - 1%"))
    )
    (comp (ref "R51")
      (value "0*")
      (footprint "RESC1608X55N")
      (description "Resistor - 1%")
      (fields
        (field (name "PART NUMBER") "R0603_0R_JUMPER")
        (field (name "MANUFACTURER") "GENERIC")
        (field (name "AUTHOR") "CERN DEM JLC")
      )
      (libsource (lib "Resistors") (part "Resistor - 1%"))
    )
    (comp (ref "R52")
      (value "470")
      (footprint "RESC1608X55N")
      (description "Resistor - 1%")
      (fields
        (field (name "PART NUMBER") "R0603_470R_1%_0.1W_100PPM")
        (field (name "POWER") "0.1W")
        (field (name "AUTHOR") "CERN DEM JLC")
      )
      (libsource (lib "Resistors") (part "Resistor - 1%"))
    )
    (comp (ref "R59")
      (value "0*")
      (footprint "RESC1608X55N")
      (description "Resistor - 1%")
      (fields
        (field (name "PART NUMBER") "R0603_0R_JUMPER")
        (field (name "MANUFACTURER") "GENERIC")
        (field (name "AUTHOR") "CERN DEM JLC")
      )
      (libsource (lib "Resistors") (part "Resistor - 1%"))
    )
    (comp (ref "R60")
      (value "200")
      (footprint "RESC1608X55N")
      (description "Resistor - 0.1%")
      (fields
        (field (name "PART NUMBER") "R0603_200R_0.1%_0.063W_10PPM")
        (field (name "POWER") "0.063W")
        (field (name "AUTHOR") "CERN DEM JLC")
      )
      (libsource (lib "Resistors") (part "Resistor - 0.1%"))
    )
    (comp (ref "R61")
      (value "200")
      (footprint "RESC1608X55N")
      (description "Resistor - 0.1%")
      (fields
        (field (name "PART NUMBER") "R0603_200R_0.1%_0.063W_10PPM")
        (field (name "POWER") "0.063W")
        (field (name "AUTHOR") "CERN DEM JLC")
      )
      (libsource (lib "Resistors") (part "Resistor - 0.1%"))
    )
    (comp (ref "R63")
      (value "4.12k")
      (footprint "RESC1608X55N")
      (description "Resistor - 0.1%")
      (fields
        (field (name "PART NUMBER") "R0603_4K12_0.1%_0.063W_10PPM")
        (field (name "POWER") "0.063W")
        (field (name "AUTHOR") "CERN DEM JLC")
      )
      (libsource (lib "Resistors") (part "Resistor - 0.1%"))
    )
    (comp (ref "R65")
      (value "22")
      (footprint "RESC1608X55N")
      (description "Resistor - 1%")
      (fields
        (field (name "PART NUMBER") "R0603_22R_1%_0.1W_100PPM")
        (field (name "POWER") "0.1W")
        (field (name "AUTHOR") "CERN DEM JLC")
      )
      (libsource (lib "Resistors") (part "Resistor - 1%"))
    )
    (comp (ref "R66")
      (value "820")
      (footprint "RESC1608X55N")
      (description "Resistor - 1%")
      (fields
        (field (name "PART NUMBER") "R0603_820R_1%_0.1W_100PPM")
        (field (name "POWER") "0.1W")
        (field (name "AUTHOR") "CERN DEM JLC")
      )
      (libsource (lib "Resistors") (part "Resistor - 1%"))
    )
    (comp (ref "R67")
      (value "390")
      (footprint "RESC1608X55N")
      (description "Resistor - 1%")
      (fields
        (field (name "PART NUMBER") "R0603_390R_1%_0.1W_100PPM")
        (field (name "POWER") "0.1W")
        (field (name "AUTHOR") "CERN DEM JLC")
      )
      (libsource (lib "Resistors") (part "Resistor - 1%"))
    )
    (comp (ref "R83")
      (value "200")
      (footprint "RESC1608X55N")
      (description "Resistor - 0.1%")
      (fields
        (field (name "PART NUMBER") "R0603_200R_0.1%_0.063W_10PPM")
        (field (name "POWER") "0.063W")
        (field (name "AUTHOR") "CERN DEM JLC")
      )
      (libsource (lib "Resistors") (part "Resistor - 0.1%"))
    )
    (comp (ref "R84")
      (value "200")
      (footprint "RESC1608X55N")
      (description "Resistor - 0.1%")
      (fields
        (field (name "PART NUMBER") "R0603_200R_0.1%_0.063W_10PPM")
        (field (name "POWER") "0.063W")
        (field (name "AUTHOR") "CERN DEM JLC")
      )
      (libsource (lib "Resistors") (part "Resistor - 0.1%"))
    )
    (comp (ref "R95")
      (value "0")
      (footprint "RESC1608X55N")
      (description "Resistor - 1%")
      (fields
        (field (name "PART NUMBER") "R0603_0R_JUMPER")
        (field (name "MANUFACTURER") "GENERIC")
        (field (name "AUTHOR") "CERN DEM JLC")
      )
      (libsource (lib "Resistors") (part "Resistor - 1%"))
    )
    (comp (ref "SJ1")
      (value "Solder joint (open)")
      (footprint "SJOINT_norm_open")
      (libsource (lib "wr_switch") (part "SOLDER_JOINT_NORM_OPEN"))
    )
    (comp (ref "SJ2")
      (value "Solder joint (open)")
      (footprint "SJOINT_norm_open")
      (libsource (lib "wr_switch") (part "SOLDER_JOINT_NORM_OPEN"))
    )
    (comp (ref "SJ3")
      (value "Solder joint (open)")
      (footprint "SJOINT_norm_open")
      (libsource (lib "wr_switch") (part "SOLDER_JOINT_NORM_OPEN"))
    )
    (comp (ref "SJ4")
      (value "Solder joint (open)")
      (footprint "SJOINT_norm_open")
      (libsource (lib "wr_switch") (part "SOLDER_JOINT_NORM_OPEN"))
    )
    (comp (ref "SJ5")
      (value "Solder joint (closed)")
      (footprint "SJOINT_norm_short")
      (libsource (lib "wr_switch") (part "SOLDER_JOINT_NORM_CLOSED"))
    )
    (comp (ref "SJ6")
      (value "Solder joint (closed)")
      (footprint "SJOINT_norm_short")
      (libsource (lib "wr_switch") (part "SOLDER_JOINT_NORM_CLOSED"))
    )
    (comp (ref "SJ7")
      (value "Solder joint (open)")
      (footprint "SJOINT_norm_open")
      (libsource (lib "wr_switch") (part "SOLDER_JOINT_NORM_OPEN"))
    )
  )
  (nets
    (net (code "1") (name "+3V3") (class "Default")
      (node (ref "C41") (pin "1") (pinfunction "1_1") (pintype "passive"))
      (node (ref "C42") (pin "1") (pinfunction "1_1") (pintype "passive"))
      (node (ref "C43") (pin "1") (pinfunction "1_1") (pintype "passive"))
      (node (ref "C44") (pin "1") (pinfunction "1_1") (pintype "passive"))
      (node (ref "C46") (pin "1") (pinfunction "1_1") (pintype "passive"))
      (node (ref "C50") (pin "1") (pinfunction "1_1") (pintype "passive"))
      (node (ref "C51") (pin "1") (pinfunction "1_1") (pintype "passive"))
      (node (ref "C58") (pin "2") (pinfunction "2_2") (pintype "passive"))
      (node (ref "C65") (pin "2") (pinfunction "2_2") (pintype "passive"))
      (node (ref "C70") (pin "1") (pinfunction "1_1") (pintype "passive"))
      (node (ref "C72") (pin "2") (pinfunction "2_2") (pintype "passive"))
      (node (ref "C73") (pin "2") (pinfunction "2_2") (pintype "passive"))
      (node (ref "IC10") (pin "5") (pinfunction "VCC/VCCO_5") (pintype "power_in"))
      (node (ref "IC12") (pin "7") (pinfunction "V+_7") (pintype "power_in"))
      (node (ref "IC13") (pin "8") (pinfunction "VDD_8") (pintype "passive"))
      (node (ref "IC14") (pin "8") (pinfunction "VDD_8") (pintype "passive"))
      (node (ref "IC6") (pin "1") (pinfunction "VCC_OUT_1") (pintype "power_in"))
      (node (ref "IC6") (pin "20") (pinfunction "VCC_IN_20") (pintype "power_in"))
      (node (ref "IC6") (pin "27") (pinfunction "VCC_OUT_27") (pintype "power_in"))
      (node (ref "IC6") (pin "30") (pinfunction "VCC_OUT_30") (pintype "power_in"))
      (node (ref "IC6") (pin "4") (pinfunction "VCC_OUT_4") (pintype "power_in"))
      (node (ref "IC6") (pin "7") (pinfunction "CE_7") (pintype "input"))
      (node (ref "IC8") (pin "14") (pinfunction "VDD_14") (pintype "passive"))
      (node (ref "L7") (pin "2") (pinfunction "2_2") (pintype "passive"))
      (node (ref "R25") (pin "2") (pinfunction "2_2") (pintype "passive"))
      (node (ref "R39") (pin "2") (pinfunction "2_2") (pintype "passive"))
    )
    (net (code "2") (name "+3V3_OSC") (class "Default")
      (node (ref "C52") (pin "1") (pinfunction "1_1") (pintype "passive"))
      (node (ref "C53") (pin "1") (pinfunction "1_1") (pintype "passive"))
      (node (ref "C54") (pin "1") (pinfunction "1_1") (pintype "passive"))
      (node (ref "C59") (pin "1") (pinfunction "1_1") (pintype "passive"))
      (node (ref "C61") (pin "1") (pinfunction "1_1") (pintype "passive"))
      (node (ref "C63") (pin "1") (pinfunction "1_1") (pintype "passive"))
      (node (ref "C66") (pin "1") (pinfunction "1_1") (pintype "passive"))
      (node (ref "C67") (pin "1") (pinfunction "1_1") (pintype "passive"))
      (node (ref "C68") (pin "1") (pinfunction "1_1") (pintype "passive"))
      (node (ref "C69") (pin "1") (pinfunction "1_1") (pintype "passive"))
      (node (ref "C77") (pin "1") (pinfunction "1_1") (pintype "passive"))
      (node (ref "C79") (pin "1") (pinfunction "1_1") (pintype "passive"))
      (node (ref "C80") (pin "1") (pinfunction "1_1") (pintype "passive"))
      (node (ref "C83") (pin "1") (pinfunction "1_1") (pintype "passive"))
      (node (ref "C86") (pin "1") (pinfunction "1_1") (pintype "passive"))
      (node (ref "C88") (pin "1") (pinfunction "1_1") (pintype "passive"))
      (node (ref "C98") (pin "1") (pinfunction "1_1") (pintype "passive"))
      (node (ref "IC15") (pin "1") (pinfunction "VDD_1") (pintype "power_in"))
      (node (ref "IC18") (pin "1") (pinfunction "VDD_1") (pintype "power_in"))
      (node (ref "IC7") (pin "1") (pinfunction "VS_1") (pintype "power_in"))
      (node (ref "IC7") (pin "11") (pinfunction "VS_11") (pintype "power_in"))
      (node (ref "IC7") (pin "12") (pinfunction "VS_12") (pintype "power_in"))
      (node (ref "IC7") (pin "24") (pinfunction "~{PD}_24") (pintype "input"))
      (node (ref "IC7") (pin "27") (pinfunction "VS_DRV_27") (pintype "power_in"))
      (node (ref "IC7") (pin "30") (pinfunction "VS_30") (pintype "power_in"))
      (node (ref "IC7") (pin "31") (pinfunction "VS_31") (pintype "power_in"))
      (node (ref "IC7") (pin "32") (pinfunction "VS_32") (pintype "power_in"))
      (node (ref "IC7") (pin "38") (pinfunction "VS_38") (pintype "power_in"))
      (node (ref "IC7") (pin "41") (pinfunction "VS_DRV_41") (pintype "power_in"))
      (node (ref "IC7") (pin "49") (pinfunction "VS_49") (pintype "power_in"))
      (node (ref "IC7") (pin "50") (pinfunction "VS_50") (pintype "power_in"))
      (node (ref "IC7") (pin "51") (pinfunction "VS_51") (pintype "power_in"))
      (node (ref "IC7") (pin "54") (pinfunction "VS_DRV_54") (pintype "power_in"))
      (node (ref "IC7") (pin "57") (pinfunction "VS_57") (pintype "power_in"))
      (node (ref "IC7") (pin "60") (pinfunction "VS_60") (pintype "power_in"))
      (node (ref "IC7") (pin "61") (pinfunction "VS_61") (pintype "power_in"))
      (node (ref "IC9") (pin "2") (pinfunction "Enable_2") (pintype "input"))
      (node (ref "L15") (pin "2") (pinfunction "2_2") (pintype "passive"))
      (node (ref "L5") (pin "2") (pinfunction "2_2") (pintype "passive"))
      (node (ref "L6") (pin "2") (pinfunction "2_2") (pintype "passive"))
    )
    (net (code "3") (name "+5V") (class "Default")
      (node (ref "IC17") (pin "2") (pinfunction "IN_2") (pintype "power_in"))
    )
    (net (code "4") (name "/DAC_DMTD_DIN") (class "Default")
      (node (ref "IC18") (pin "7") (pinfunction "DIN_7") (pintype "input"))
    )
    (net (code "5") (name "/DAC_DMTD_SCLK") (class "Default")
      (node (ref "IC18") (pin "6") (pinfunction "SCLK_6") (pintype "input"))
    )
    (net (code "6") (name "/DAC_DMTD_SYNC") (class "Default")
      (node (ref "IC18") (pin "5") (pinfunction "/SYNC_5") (pintype "input"))
    )
    (net (code "7") (name "/DAC_REF_DIN") (class "Default")
      (node (ref "IC15") (pin "7") (pinfunction "DIN_7") (pintype "input"))
    )
    (net (code "8") (name "/DAC_REF_SCLK") (class "Default")
      (node (ref "IC15") (pin "6") (pinfunction "SCLK_6") (pintype "input"))
    )
    (net (code "9") (name "/DAC_REF_SYNC") (class "Default")
      (node (ref "IC15") (pin "5") (pinfunction "/SYNC_5") (pintype "input"))
    )
    (net (code "10") (name "/DMTDCLK_FAN_N") (class "Default")
      (node (ref "IC6") (pin "5") (pinfunction "OUTN0_5") (pintype "output"))
    )
    (net (code "11") (name "/DMTDCLK_FAN_P") (class "Default")
      (node (ref "IC6") (pin "6") (pinfunction "OUTP0_6") (pintype "output"))
    )
    (net (code "12") (name "/DMTDCLK_FB_N") (class "Default")
      (node (ref "IC6") (pin "2") (pinfunction "OUTN1_2") (pintype "output"))
    )
    (net (code "13") (name "/DMTDCLK_FB_P") (class "Default")
      (node (ref "IC6") (pin "3") (pinfunction "OUTP1_3") (pintype "output"))
    )
    (net (code "14") (name "/DMTDCLK_MAIN_N") (class "Default")
      (node (ref "IC6") (pin "31") (pinfunction "OUTN2_31") (pintype "output"))
    )
    (net (code "15") (name "/DMTDCLK_MAIN_P") (class "Default")
      (node (ref "IC6") (pin "32") (pinfunction "OUTP2_32") (pintype "output"))
    )
    (net (code "16") (name "/EXT125_N") (class "Default")
      (node (ref "C105") (pin "2") (pinfunction "2_2") (pintype "passive"))
      (node (ref "IC7") (pin "14") (pinfunction "~{CLK}_14") (pintype "input"))
      (node (ref "R49") (pin "1") (pinfunction "1_1") (pintype "passive"))
    )
    (net (code "17") (name "/EXT125_P") (class "Default")
      (node (ref "C104") (pin "2") (pinfunction "2_2") (pintype "passive"))
      (node (ref "IC7") (pin "13") (pinfunction "CLK_13") (pintype "input"))
      (node (ref "R49") (pin "2") (pinfunction "2_2") (pintype "passive"))
    )
    (net (code "18") (name "/EXTPPSIN") (class "Default")
      (node (ref "IC8") (pin "2") (pinfunction "B_2") (pintype "input"))
      (node (ref "R30") (pin "2") (pinfunction "2_2") (pintype "passive"))
    )
    (net (code "19") (name "/EXTPPSOUT") (class "Default")
      (node (ref "R32") (pin "1") (pinfunction "1_1") (pintype "passive"))
    )
    (net (code "20") (name "/EXTREFIN_10M") (class "Default")
      (node (ref "C60") (pin "1") (pinfunction "1_1") (pintype "passive"))
      (node (ref "R33") (pin "2") (pinfunction "2_2") (pintype "passive"))
      (node (ref "R34") (pin "2") (pinfunction "2_2") (pintype "passive"))
    )
    (net (code "21") (name "/EXTREFIN_125M") (class "Default")
      (node (ref "C78") (pin "1") (pinfunction "1_1") (pintype "passive"))
      (node (ref "R41") (pin "2") (pinfunction "2_2") (pintype "passive"))
      (node (ref "R42") (pin "2") (pinfunction "2_2") (pintype "passive"))
    )
    (net (code "22") (name "/EXTREFOUT") (class "Default")
      (node (ref "R46") (pin "1") (pinfunction "1_1") (pintype "passive"))
    )
    (net (code "23") (name "/EXTREF_N") (class "Default")
      (node (ref "C165") (pin "2") (pinfunction "2_2") (pintype "passive"))
      (node (ref "IC14") (pin "3") (pinfunction "/D_3") (pintype "input"))
      (node (ref "R47") (pin "2") (pinfunction "2_2") (pintype "passive"))
    )
    (net (code "24") (name "/EXTREF_P") (class "Default")
      (node (ref "C166") (pin "2") (pinfunction "2_2") (pintype "passive"))
      (node (ref "IC14") (pin "2") (pinfunction "D_2") (pintype "input"))
      (node (ref "R47") (pin "1") (pinfunction "1_1") (pintype "passive"))
    )
    (net (code "25") (name "/EXT_VBB") (class "Default")
      (node (ref "C74") (pin "1") (pinfunction "1_1") (pintype "passive"))
      (node (ref "IC12") (pin "3") (pinfunction "IN+_3") (pintype "input"))
      (node (ref "IC13") (pin "4") (pinfunction "VBB_4") (pintype "passive"))
    )
    (net (code "26") (name "/PLL_CS") (class "Default")
      (node (ref "IC7") (pin "17") (pinfunction "~{CS}_17") (pintype "input"))
    )
    (net (code "27") (name "/PLL_LOCK") (class "Default")
      (node (ref "IC7") (pin "3") (pinfunction "LD_3") (pintype "output"))
    )
    (net (code "28") (name "/PLL_REFSEL") (class "Default")
      (node (ref "IC7") (pin "7") (pinfunction "REF_SEL_7") (pintype "input"))
    )
    (net (code "29") (name "/PLL_RESET") (class "Default")
      (node (ref "IC6") (pin "12") (pinfunction "~{RSTN}_12") (pintype "input"))
      (node (ref "IC7") (pin "23") (pinfunction "~{RESET}_23") (pintype "input"))
    )
    (net (code "30") (name "/PLL_SCLK") (class "Default")
      (node (ref "IC7") (pin "16") (pinfunction "SCLK_16") (pintype "input"))
    )
    (net (code "31") (name "/PLL_SDI") (class "Default")
      (node (ref "IC7") (pin "22") (pinfunction "SDIO_22") (pintype "bidirectional"))
    )
    (net (code "32") (name "/PLL_SDO") (class "Default")
      (node (ref "IC7") (pin "21") (pinfunction "SDO_21") (pintype "output"))
    )
    (net (code "33") (name "/PLL_STAT") (class "Default")
      (node (ref "R65") (pin "2") (pinfunction "2_2") (pintype "passive"))
    )
    (net (code "34") (name "/PPS_IN") (class "Default")
      (node (ref "IC8") (pin "5") (pinfunction "B_5") (pintype "input"))
    )
    (net (code "35") (name "/PPS_OUT") (class "Default")
      (node (ref "R26") (pin "2") (pinfunction "2_2") (pintype "passive"))
    )
    (net (code "36") (name "/REFCLK_FAN_N") (class "Default")
      (node (ref "IC7") (pin "47") (pinfunction "~{OUT6}_(OUT6B)_47") (pintype "output"))
    )
    (net (code "37") (name "/REFCLK_FAN_P") (class "Default")
      (node (ref "IC7") (pin "48") (pinfunction "OUT6_(OUT6A)_48") (pintype "output"))
    )
    (net (code "38") (name "/REFCLK_FB_N") (class "Default")
      (node (ref "IC7") (pin "45") (pinfunction "~{OUT7}_(OUT7B)_45") (pintype "output"))
    )
    (net (code "39") (name "/REFCLK_FB_P") (class "Default")
      (node (ref "IC7") (pin "46") (pinfunction "OUT7_(OUT7A)_46") (pintype "output"))
    )
    (net (code "40") (name "/REFCLK_MAIN_N") (class "Default")
      (node (ref "IC7") (pin "34") (pinfunction "~{OUT8}_(OUT8B)_34") (pintype "output"))
    )
    (net (code "41") (name "/REFCLK_MAIN_P") (class "Default")
      (node (ref "IC7") (pin "33") (pinfunction "OUT8_(OUT8A)_33") (pintype "output"))
    )
    (net (code "42") (name "/REFCLK_UP0") (class "Default")
      (node (ref "R36") (pin "2") (pinfunction "2_2") (pintype "passive"))
    )
    (net (code "43") (name "/REFCLK_UP1") (class "Default")
      (node (ref "R43") (pin "2") (pinfunction "2_2") (pintype "passive"))
    )
    (net (code "44") (name "/REF_10M") (class "Default")
      (node (ref "C4") (pin "2") (pinfunction "2_2") (pintype "passive"))
      (node (ref "R35") (pin "2") (pinfunction "2_2") (pintype "passive"))
    )
    (net (code "45") (name "GND") (class "Default")
      (node (ref "C101") (pin "1") (pinfunction "1_1") (pintype "passive"))
      (node (ref "C102") (pin "2") (pinfunction "2_2") (pintype "passive"))
      (node (ref "C124") (pin "1") (pinfunction "1_1") (pintype "passive"))
      (node (ref "C162") (pin "1") (pinfunction "1_1") (pintype "passive"))
      (node (ref "C41") (pin "2") (pinfunction "2_2") (pintype "passive"))
      (node (ref "C42") (pin "2") (pinfunction "2_2") (pintype "passive"))
      (node (ref "C43") (pin "2") (pinfunction "2_2") (pintype "passive"))
      (node (ref "C44") (pin "2") (pinfunction "2_2") (pintype "passive"))
      (node (ref "C45") (pin "2") (pinfunction "2_2") (pintype "passive"))
      (node (ref "C46") (pin "2") (pinfunction "2_2") (pintype "passive"))
      (node (ref "C47") (pin "2") (pinfunction "2_2") (pintype "passive"))
      (node (ref "C48") (pin "2") (pinfunction "2_2") (pintype "passive"))
      (node (ref "C49") (pin "2") (pinfunction "2_2") (pintype "passive"))
      (node (ref "C50") (pin "2") (pinfunction "2_2") (pintype "passive"))
      (node (ref "C51") (pin "2") (pinfunction "2_2") (pintype "passive"))
      (node (ref "C52") (pin "2") (pinfunction "2_2") (pintype "passive"))
      (node (ref "C53") (pin "2") (pinfunction "2_2") (pintype "passive"))
      (node (ref "C54") (pin "2") (pinfunction "2_2") (pintype "passive"))
      (node (ref "C55") (pin "1") (pinfunction "1_1") (pintype "passive"))
      (node (ref "C56") (pin "1") (pinfunction "1_1") (pintype "passive"))
      (node (ref "C58") (pin "1") (pinfunction "1_1") (pintype "passive"))
      (node (ref "C59") (pin "2") (pinfunction "2_2") (pintype "passive"))
      (node (ref "C61") (pin "2") (pinfunction "2_2") (pintype "passive"))
      (node (ref "C62") (pin "2") (pinfunction "2_2") (pintype "passive"))
      (node (ref "C63") (pin "2") (pinfunction "2_2") (pintype "passive"))
      (node (ref "C64") (pin "1") (pinfunction "1_1") (pintype "passive"))
      (node (ref "C65") (pin "1") (pinfunction "1_1") (pintype "passive"))
      (node (ref "C66") (pin "2") (pinfunction "2_2") (pintype "passive"))
      (node (ref "C67") (pin "2") (pinfunction "2_2") (pintype "passive"))
      (node (ref "C68") (pin "2") (pinfunction "2_2") (pintype "passive"))
      (node (ref "C69") (pin "2") (pinfunction "2_2") (pintype "passive"))
      (node (ref "C70") (pin "2") (pinfunction "2_2") (pintype "passive"))
      (node (ref "C72") (pin "1") (pinfunction "1_1") (pintype "passive"))
      (node (ref "C73") (pin "1") (pinfunction "1_1") (pintype "passive"))
      (node (ref "C74") (pin "2") (pinfunction "2_2") (pintype "passive"))
      (node (ref "C75") (pin "1") (pinfunction "1_1") (pintype "passive"))
      (node (ref "C76") (pin "2") (pinfunction "2_2") (pintype "passive"))
      (node (ref "C77") (pin "2") (pinfunction "2_2") (pintype "passive"))
      (node (ref "C79") (pin "2") (pinfunction "2_2") (pintype "passive"))
      (node (ref "C80") (pin "2") (pinfunction "2_2") (pintype "passive"))
      (node (ref "C81") (pin "2") (pinfunction "2_2") (pintype "passive"))
      (node (ref "C82") (pin "2") (pinfunction "2_2") (pintype "passive"))
      (node (ref "C83") (pin "2") (pinfunction "2_2") (pintype "passive"))
      (node (ref "C84") (pin "2") (pinfunction "2_2") (pintype "passive"))
      (node (ref "C85") (pin "1") (pinfunction "1_1") (pintype "passive"))
      (node (ref "C86") (pin "2") (pinfunction "2_2") (pintype "passive"))
      (node (ref "C87") (pin "1") (pinfunction "1_1") (pintype "passive"))
      (node (ref "C88") (pin "2") (pinfunction "2_2") (pintype "passive"))
      (node (ref "C89") (pin "1") (pinfunction "1_1") (pintype "passive"))
      (node (ref "C90") (pin "1") (pinfunction "1_1") (pintype "passive"))
      (node (ref "C91") (pin "1") (pinfunction "1_1") (pintype "passive"))
      (node (ref "C92") (pin "1") (pinfunction "1_1") (pintype "passive"))
      (node (ref "C93") (pin "1") (pinfunction "1_1") (pintype "passive"))
      (node (ref "C94") (pin "1") (pinfunction "1_1") (pintype "passive"))
      (node (ref "C95") (pin "1") (pinfunction "1_1") (pintype "passive"))
      (node (ref "C96") (pin "1") (pinfunction "1_1") (pintype "passive"))
      (node (ref "C97") (pin "2") (pinfunction "2_2") (pintype "passive"))
      (node (ref "C98") (pin "2") (pinfunction "2_2") (pintype "passive"))
      (node (ref "C99") (pin "1") (pinfunction "1_1") (pintype "passive"))
      (node (ref "CT1") (pin "2") (pintype "passive"))
      (node (ref "CT10") (pin "2") (pintype "passive"))
      (node (ref "CT2") (pin "2") (pintype "passive"))
      (node (ref "CT3") (pin "2") (pintype "passive"))
      (node (ref "CT5") (pin "2") (pintype "passive"))
      (node (ref "CT6") (pin "2") (pintype "passive"))
      (node (ref "IC10") (pin "2") (pinfunction "VEE_2") (pintype "power_in"))
      (node (ref "IC11") (pin "2") (pinfunction "GND_2") (pintype "power_in"))
      (node (ref "IC12") (pin "4") (pinfunction "V-_4") (pintype "power_in"))
      (node (ref "IC13") (pin "5") (pinfunction "VEE_5") (pintype "passive"))
      (node (ref "IC14") (pin "5") (pinfunction "GND_5") (pintype "passive"))
      (node (ref "IC15") (pin "8") (pinfunction "GND_8") (pintype "power_in"))
      (node (ref "IC17") (pin "4") (pinfunction "GND_4") (pintype "power_in"))
      (node (ref "IC17") (pin "8") (pinfunction "SEL_8") (pintype "input"))
      (node (ref "IC18") (pin "8") (pinfunction "GND_8") (pintype "power_in"))
      (node (ref "IC6") (pin "10") (pinfunction "OS1_10") (pintype "input"))
      (node (ref "IC6") (pin "15") (pinfunction "OD2_15") (pintype "input"))
      (node (ref "IC6") (pin "22") (pinfunction "GND1_22") (pintype "power_in"))
      (node (ref "IC6") (pin "PAD") (pinfunction "GND_PAD") (pintype "power_in"))
      (node (ref "IC7") (pin "37") (pinfunction "GND_37") (pintype "power_in"))
      (node (ref "IC7") (pin "44") (pinfunction "GND_44") (pintype "power_in"))
      (node (ref "IC7") (pin "59") (pinfunction "GND_59") (pintype "power_in"))
      (node (ref "IC7") (pin "PAD") (pinfunction "GND_PAD_PAD") (pintype "power_in"))
      (node (ref "IC8") (pin "1") (pinfunction "~{A}_1") (pintype "input"))
      (node (ref "IC8") (pin "4") (pinfunction "~{A}_4") (pintype "input"))
      (node (ref "IC8") (pin "7") (pinfunction "GND_7") (pintype "passive"))
      (node (ref "IC9") (pin "3") (pinfunction "GND_3") (pintype "power_in"))
      (node (ref "R27") (pin "1") (pinfunction "1_1") (pintype "passive"))
      (node (ref "R30") (pin "1") (pinfunction "1_1") (pintype "passive"))
      (node (ref "R50") (pin "1") (pinfunction "1_1") (pintype "passive"))
      (node (ref "R60") (pin "2") (pinfunction "2_2") (pintype "passive"))
      (node (ref "R61") (pin "1") (pinfunction "1_1") (pintype "passive"))
      (node (ref "R63") (pin "1") (pinfunction "1_1") (pintype "passive"))
      (node (ref "R83") (pin "2") (pinfunction "2_2") (pintype "passive"))
      (node (ref "R84") (pin "1") (pinfunction "1_1") (pintype "passive"))
      (node (ref "SJ1") (pin "1") (pinfunction "P1_1") (pintype "passive"))
      (node (ref "SJ2") (pin "1") (pinfunction "P1_1") (pintype "passive"))
      (node (ref "SJ3") (pin "1") (pinfunction "P1_1") (pintype "passive"))
      (node (ref "SJ4") (pin "1") (pinfunction "P1_1") (pintype "passive"))
      (node (ref "SJ5") (pin "1") (pinfunction "P1_1") (pintype "passive"))
      (node (ref "SJ5") (pin "2") (pinfunction "P2_2") (pintype "passive"))
      (node (ref "SJ6") (pin "1") (pinfunction "P1_1") (pintype "passive"))
      (node (ref "SJ6") (pin "2") (pinfunction "P2_2") (pintype "passive"))
      (node (ref "SJ7") (pin "1") (pinfunction "P1_1") (pintype "passive"))
    )
    (net (code "46") (name "Net-(C55-Pad2)") (class "Default")
      (node (ref "C55") (pin "2") (pinfunction "2_2") (pintype "passive"))
      (node (ref "C56") (pin "2") (pinfunction "2_2") (pintype "passive"))
      (node (ref "R25") (pin "1") (pinfunction "1_1") (pintype "passive"))
      (node (ref "R27") (pin "2") (pinfunction "2_2") (pintype "passive"))
      (node (ref "R28") (pin "2") (pinfunction "2_2") (pintype "passive"))
      (node (ref "R29") (pin "2") (pinfunction "2_2") (pintype "passive"))
    )
    (net (code "47") (name "Net-(C60-Pad2)") (class "Default")
      (node (ref "C60") (pin "2") (pinfunction "2_2") (pintype "passive"))
      (node (ref "R31") (pin "1") (pinfunction "1_1") (pintype "passive"))
    )
    (net (code "48") (name "Net-(C62-Pad1)") (class "Default")
      (node (ref "C62") (pin "1") (pinfunction "1_1") (pintype "passive"))
      (node (ref "R33") (pin "1") (pinfunction "1_1") (pintype "passive"))
      (node (ref "R34") (pin "1") (pinfunction "1_1") (pintype "passive"))
    )
    (net (code "49") (name "Net-(C78-Pad2)") (class "Default")
      (node (ref "C78") (pin "2") (pinfunction "2_2") (pintype "passive"))
      (node (ref "R40") (pin "1") (pinfunction "1_1") (pintype "passive"))
    )
    (net (code "50") (name "Net-(C82-Pad1)") (class "Default")
      (node (ref "C82") (pin "1") (pinfunction "1_1") (pintype "passive"))
      (node (ref "R41") (pin "1") (pinfunction "1_1") (pintype "passive"))
      (node (ref "R42") (pin "1") (pinfunction "1_1") (pintype "passive"))
    )
    (net (code "51") (name "Net-(C160-Pad1)") (class "Default")
      (node (ref "C160") (pin "1") (pinfunction "1_1") (pintype "passive"))
      (node (ref "R66") (pin "2") (pinfunction "2_2") (pintype "passive"))
    )
    (net (code "52") (name "Net-(CT1-Pad1)") (class "Default")
      (node (ref "CT1") (pin "1") (pintype "passive"))
      (node (ref "R17") (pin "2") (pinfunction "2_2") (pintype "passive"))
    )
    (net (code "53") (name "Net-(CT3-Pad1)") (class "Default")
      (node (ref "CT3") (pin "1") (pintype "passive"))
      (node (ref "R48") (pin "1") (pinfunction "1_1") (pintype "passive"))
    )
    (net (code "54") (name "Net-(CT5-Pad1)") (class "Default")
      (node (ref "CT5") (pin "1") (pintype "passive"))
      (node (ref "R51") (pin "2") (pinfunction "2_2") (pintype "passive"))
    )
    (net (code "55") (name "Net-(CT6-Pad1)") (class "Default")
      (node (ref "CT6") (pin "1") (pintype "passive"))
      (node (ref "R95") (pin "2") (pinfunction "2_2") (pintype "passive"))
    )
    (net (code "56") (name "Net-(CT10-Pad1)") (class "Default")
      (node (ref "CT10") (pin "1") (pintype "passive"))
      (node (ref "R59") (pin "2") (pinfunction "2_2") (pintype "passive"))
    )
    (net (code "57") (name "Net-(D3-A)") (class "Default")
      (node (ref "C64") (pin "2") (pinfunction "2_2") (pintype "passive"))
      (node (ref "D3") (pin "1") (pinfunction "A_1") (pintype "passive"))
      (node (ref "D3") (pin "2") (pinfunction "K_2") (pintype "passive"))
    )
    (net (code "58") (name "Net-(D3-C)") (class "Default")
      (node (ref "D3") (pin "3") (pinfunction "C_3") (pintype "passive"))
      (node (ref "IC10") (pin "3") (pinfunction "VP_3") (pintype "input"))
      (node (ref "R28") (pin "1") (pinfunction "1_1") (pintype "passive"))
      (node (ref "R31") (pin "2") (pinfunction "2_2") (pintype "passive"))
    )
    (net (code "59") (name "Net-(D4-A)") (class "Default")
      (node (ref "C84") (pin "1") (pinfunction "1_1") (pintype "passive"))
      (node (ref "D4") (pin "1") (pinfunction "A_1") (pintype "passive"))
      (node (ref "D4") (pin "2") (pinfunction "K_2") (pintype "passive"))
    )
    (net (code "60") (name "Net-(D4-C)") (class "Default")
      (node (ref "D4") (pin "3") (pinfunction "C_3") (pintype "passive"))
      (node (ref "IC13") (pin "2") (pinfunction "D_2") (pintype "input"))
      (node (ref "R38") (pin "1") (pinfunction "1_1") (pintype "passive"))
      (node (ref "R40") (pin "2") (pinfunction "2_2") (pintype "passive"))
    )
    (net (code "61") (name "Net-(IC6A-OD0)") (class "Default")
      (node (ref "IC6") (pin "13") (pinfunction "OD0_13") (pintype "input"))
      (node (ref "SJ3") (pin "2") (pinfunction "P2_2") (pintype "passive"))
    )
    (net (code "62") (name "Net-(IC6A-OD1)") (class "Default")
      (node (ref "IC6") (pin "14") (pinfunction "OD1_14") (pintype "input"))
      (node (ref "SJ4") (pin "2") (pinfunction "P2_2") (pintype "passive"))
    )
    (net (code "63") (name "Net-(IC6A-OS0)") (class "Default")
      (node (ref "IC6") (pin "11") (pinfunction "OS0_11") (pintype "input"))
      (node (ref "SJ7") (pin "2") (pinfunction "P2_2") (pintype "passive"))
    )
    (net (code "64") (name "Net-(IC6A-OUTN3)") (class "Default")
      (node (ref "IC6") (pin "28") (pinfunction "OUTN3_28") (pintype "output"))
      (node (ref "R44") (pin "1") (pinfunction "1_1") (pintype "passive"))
    )
    (net (code "65") (name "Net-(IC6A-OUTP3)") (class "Default")
      (node (ref "CT2") (pin "1") (pintype "passive"))
      (node (ref "IC6") (pin "29") (pinfunction "OUTP3_29") (pintype "output"))
      (node (ref "R44") (pin "2") (pinfunction "2_2") (pintype "passive"))
    )
    (net (code "66") (name "Net-(IC6A-PR0)") (class "Default")
      (node (ref "IC6") (pin "25") (pinfunction "PR0_25") (pintype "input"))
      (node (ref "SJ2") (pin "2") (pinfunction "P2_2") (pintype "passive"))
    )
    (net (code "67") (name "Net-(IC6A-PR1)") (class "Default")
      (node (ref "IC6") (pin "26") (pinfunction "PR1_26") (pintype "input"))
      (node (ref "SJ1") (pin "2") (pinfunction "P2_2") (pintype "passive"))
    )
    (net (code "68") (name "Net-(IC6A-REG_CAP1)") (class "Default")
      (node (ref "C97") (pin "1") (pinfunction "1_1") (pintype "passive"))
      (node (ref "IC6") (pin "19") (pinfunction "REG_CAP1_19") (pintype "passive"))
    )
    (net (code "69") (name "Net-(IC6A-REG_CAP2)") (class "Default")
      (node (ref "C102") (pin "1") (pinfunction "1_1") (pintype "passive"))
      (node (ref "IC6") (pin "17") (pinfunction "REG_CAP2_17") (pintype "passive"))
    )
    (net (code "70") (name "Net-(IC6A-XIN)") (class "Default")
      (node (ref "C100") (pin "2") (pinfunction "2_2") (pintype "passive"))
      (node (ref "IC6") (pin "21") (pinfunction "XIN_21") (pintype "input"))
    )
    (net (code "71") (name "Net-(IC6B-VCC_PLL1)") (class "Default")
      (node (ref "C45") (pin "1") (pinfunction "1_1") (pintype "passive"))
      (node (ref "C47") (pin "1") (pinfunction "1_1") (pintype "passive"))
      (node (ref "C48") (pin "1") (pinfunction "1_1") (pintype "passive"))
      (node (ref "C49") (pin "1") (pinfunction "1_1") (pintype "passive"))
      (node (ref "IC6") (pin "16") (pinfunction "VCC_PLL2_16") (pintype "power_in"))
      (node (ref "IC6") (pin "18") (pinfunction "VCC_PLL1_18") (pintype "power_in"))
      (node (ref "IC6") (pin "9") (pinfunction "VCC_VCO_9") (pintype "power_in"))
      (node (ref "L7") (pin "1") (pinfunction "1_1") (pintype "passive"))
    )
    (net (code "72") (name "Net-(IC7A-BYPASS)") (class "Default")
      (node (ref "C127") (pin "1") (pinfunction "1_1") (pintype "passive"))
      (node (ref "C161") (pin "1") (pinfunction "1_1") (pintype "passive"))
      (node (ref "C162") (pin "2") (pinfunction "2_2") (pintype "passive"))
      (node (ref "IC7") (pin "10") (pinfunction "BYPASS_10") (pintype "output"))
      (node (ref "R66") (pin "1") (pinfunction "1_1") (pintype "passive"))
    )
    (net (code "73") (name "Net-(IC7A-CP)") (class "Default")
      (node (ref "C127") (pin "2") (pinfunction "2_2") (pintype "passive"))
      (node (ref "C160") (pin "2") (pinfunction "2_2") (pintype "passive"))
      (node (ref "IC7") (pin "5") (pinfunction "CP_5") (pintype "output"))
      (node (ref "R67") (pin "2") (pinfunction "2_2") (pintype "passive"))
    )
    (net (code "74") (name "Net-(IC7A-CPRSET)") (class "Default")
      (node (ref "IC7") (pin "62") (pinfunction "CPRSET_62") (pintype "passive"))
      (node (ref "R50") (pin "2") (pinfunction "2_2") (pintype "passive"))
    )
    (net (code "75") (name "Net-(IC7A-LF)") (class "Default")
      (node (ref "C161") (pin "2") (pinfunction "2_2") (pintype "passive"))
      (node (ref "IC7") (pin "9") (pinfunction "LF_9") (pintype "input"))
      (node (ref "R67") (pin "1") (pinfunction "1_1") (pintype "passive"))
    )
    (net (code "76") (name "Net-(IC7A-OUT5)") (class "Default")
      (node (ref "C166") (pin "1") (pinfunction "1_1") (pintype "passive"))
      (node (ref "IC7") (pin "28") (pinfunction "OUT5_28") (pintype "output"))
      (node (ref "R84") (pin "2") (pinfunction "2_2") (pintype "passive"))
    )
    (net (code "77") (name "Net-(IC7A-OUT9_(OUT9A))") (class "Default")
      (node (ref "IC7") (pin "35") (pinfunction "OUT9_(OUT9A)_35") (pintype "output"))
      (node (ref "R36") (pin "1") (pinfunction "1_1") (pintype "passive"))
    )
    (net (code "78") (name "Net-(IC7A-REFIN_(REF1))") (class "Default")
      (node (ref "C103") (pin "1") (pinfunction "1_1") (pintype "passive"))
      (node (ref "IC7") (pin "64") (pinfunction "REFIN_(REF1)_64") (pintype "input"))
    )
    (net (code "79") (name "Net-(IC7A-RSET)") (class "Default")
      (node (ref "IC7") (pin "58") (pinfunction "RSET_58") (pintype "passive"))
      (node (ref "R63") (pin "2") (pinfunction "2_2") (pintype "passive"))
    )
    (net (code "80") (name "Net-(IC7A-STATUS)") (class "Default")
      (node (ref "IC7") (pin "6") (pinfunction "STATUS_6") (pintype "output"))
      (node (ref "R65") (pin "1") (pinfunction "1_1") (pintype "passive"))
      (node (ref "R95") (pin "1") (pinfunction "1_1") (pintype "passive"))
    )
    (net (code "81") (name "Net-(IC7A-~{OUT5})") (class "Default")
      (node (ref "C165") (pin "1") (pinfunction "1_1") (pintype "passive"))
      (node (ref "IC7") (pin "29") (pinfunction "~{OUT5}_29") (pintype "output"))
      (node (ref "R83") (pin "1") (pinfunction "1_1") (pintype "passive"))
    )
    (net (code "82") (name "Net-(IC7A-~{OUT9}_(OUT9B))") (class "Default")
      (node (ref "IC7") (pin "36") (pinfunction "~{OUT9}_(OUT9B)_36") (pintype "output"))
      (node (ref "R43") (pin "1") (pinfunction "1_1") (pintype "passive"))
    )
    (net (code "83") (name "Net-(IC7A-~{REFIN}_(REF2))") (class "Default")
      (node (ref "C4") (pin "1") (pinfunction "1_1") (pintype "passive"))
      (node (ref "IC7") (pin "63") (pinfunction "~{REFIN}_(REF2)_63") (pintype "input"))
    )
    (net (code "84") (name "Net-(IC7B-VCP)") (class "Default")
      (node (ref "C89") (pin "2") (pinfunction "2_2") (pintype "passive"))
      (node (ref "C92") (pin "2") (pinfunction "2_2") (pintype "passive"))
      (node (ref "C95") (pin "2") (pinfunction "2_2") (pintype "passive"))
      (node (ref "IC7") (pin "4") (pinfunction "VCP_4") (pintype "power_in"))
      (node (ref "L15") (pin "1") (pinfunction "1_1") (pintype "passive"))
    )
    (net (code "85") (name "Net-(IC8A-Y)") (class "Default")
      (node (ref "IC8") (pin "3") (pinfunction "Y_3") (pintype "tri_state"))
      (node (ref "R26") (pin "1") (pinfunction "1_1") (pintype "passive"))
    )
    (net (code "86") (name "Net-(IC8B-Y)") (class "Default")
      (node (ref "IC8") (pin "6") (pinfunction "Y_6") (pintype "tri_state"))
      (node (ref "R32") (pin "2") (pinfunction "2_2") (pintype "passive"))
    )
    (net (code "87") (name "Net-(IC9-+Vs)") (class "Default")
      (node (ref "C96") (pin "2") (pinfunction "2_2") (pintype "passive"))
      (node (ref "C99") (pin "2") (pinfunction "2_2") (pintype "passive"))
      (node (ref "IC9") (pin "6") (pinfunction "+Vs_6") (pintype "power_in"))
      (node (ref "L5") (pin "1") (pinfunction "1_1") (pintype "passive"))
    )
    (net (code "88") (name "Net-(IC9-OUT)") (class "Default")
      (node (ref "C100") (pin "1") (pinfunction "1_1") (pintype "passive"))
      (node (ref "IC9") (pin "4") (pinfunction "OUT_4") (pintype "output"))
      (node (ref "R48") (pin "2") (pinfunction "2_2") (pintype "passive"))
    )
    (net (code "89") (name "Net-(IC9-VCtrl)") (class "Default")
      (node (ref "C101") (pin "2") (pinfunction "2_2") (pintype "passive"))
      (node (ref "C124") (pin "2") (pinfunction "2_2") (pintype "passive"))
      (node (ref "IC9") (pin "1") (pinfunction "VCtrl_1") (pintype "input"))
      (node (ref "R17") (pin "1") (pinfunction "1_1") (pintype "passive"))
      (node (ref "R52") (pin "2") (pinfunction "2_2") (pintype "passive"))
    )
    (net (code "90") (name "Net-(IC10-Q)") (class "Default")
      (node (ref "IC10") (pin "1") (pinfunction "Q_1") (pintype "open_collector"))
      (node (ref "R35") (pin "1") (pinfunction "1_1") (pintype "passive"))
    )
    (net (code "91") (name "Net-(IC10-VN)") (class "Default")
      (node (ref "IC10") (pin "4") (pinfunction "VN_4") (pintype "input"))
      (node (ref "R29") (pin "1") (pinfunction "1_1") (pintype "passive"))
    )
    (net (code "92") (name "Net-(IC11-+Vs)") (class "Default")
      (node (ref "C85") (pin "2") (pinfunction "2_2") (pintype "passive"))
      (node (ref "C87") (pin "2") (pinfunction "2_2") (pintype "passive"))
      (node (ref "IC11") (pin "4") (pinfunction "+Vs_4") (pintype "power_in"))
      (node (ref "L6") (pin "1") (pinfunction "1_1") (pintype "passive"))
    )
    (net (code "93") (name "Net-(IC11-OUT)") (class "Default")
      (node (ref "C103") (pin "2") (pinfunction "2_2") (pintype "passive"))
      (node (ref "IC11") (pin "3") (pinfunction "OUT_3") (pintype "output"))
      (node (ref "R59") (pin "1") (pinfunction "1_1") (pintype "passive"))
    )
    (net (code "94") (name "Net-(IC11-VCtrl)") (class "Default")
      (node (ref "C90") (pin "2") (pinfunction "2_2") (pintype "passive"))
      (node (ref "C91") (pin "2") (pinfunction "2_2") (pintype "passive"))
      (node (ref "IC11") (pin "1") (pinfunction "VCtrl_1") (pintype "input"))
      (node (ref "R45") (pin "2") (pinfunction "2_2") (pintype "passive"))
      (node (ref "R51") (pin "1") (pinfunction "1_1") (pintype "passive"))
    )
    (net (code "95") (name "Net-(IC12-IN-)") (class "Default")
      (node (ref "C75") (pin "2") (pinfunction "2_2") (pintype "passive"))
      (node (ref "C76") (pin "1") (pinfunction "1_1") (pintype "passive"))
      (node (ref "IC12") (pin "1") (pinfunction "OUT_1") (pintype "output"))
      (node (ref "IC12") (pin "2") (pinfunction "IN-_2") (pintype "input"))
      (node (ref "R37") (pin "2") (pinfunction "2_2") (pintype "passive"))
      (node (ref "R38") (pin "2") (pinfunction "2_2") (pintype "passive"))
    )
    (net (code "96") (name "Net-(IC13A-Q)") (class "Default")
      (node (ref "C104") (pin "1") (pinfunction "1_1") (pintype "passive"))
      (node (ref "IC13") (pin "7") (pinfunction "Q_7") (pintype "output"))
      (node (ref "R60") (pin "1") (pinfunction "1_1") (pintype "passive"))
    )
    (net (code "97") (name "Net-(IC13A-{slash}D)") (class "Default")
      (node (ref "C81") (pin "1") (pinfunction "1_1") (pintype "passive"))
      (node (ref "IC13") (pin "3") (pinfunction "/D_3") (pintype "input"))
      (node (ref "R37") (pin "1") (pinfunction "1_1") (pintype "passive"))
      (node (ref "R39") (pin "1") (pinfunction "1_1") (pintype "passive"))
    )
    (net (code "98") (name "Net-(IC13A-{slash}Q)") (class "Default")
      (node (ref "C105") (pin "1") (pinfunction "1_1") (pintype "passive"))
      (node (ref "IC13") (pin "6") (pinfunction "/Q_6") (pintype "output"))
      (node (ref "R61") (pin "2") (pinfunction "2_2") (pintype "passive"))
    )
    (net (code "99") (name "Net-(IC14A-Q)") (class "Default")
      (node (ref "IC14") (pin "7") (pinfunction "Q_7") (pintype "output"))
      (node (ref "R46") (pin "2") (pinfunction "2_2") (pintype "passive"))
    )
    (net (code "100") (name "Net-(IC15-VFB)") (class "Default")
      (node (ref "IC15") (pin "3") (pinfunction "VFB_3") (pintype "input"))
      (node (ref "IC15") (pin "4") (pinfunction "VOUT_4") (pintype "output"))
      (node (ref "R45") (pin "1") (pinfunction "1_1") (pintype "passive"))
    )
    (net (code "101") (name "Net-(IC18-VFB)") (class "Default")
      (node (ref "IC18") (pin "3") (pinfunction "VFB_3") (pintype "input"))
      (node (ref "IC18") (pin "4") (pinfunction "VOUT_4") (pintype "output"))
      (node (ref "R52") (pin "1") (pinfunction "1_1") (pintype "passive"))
    )
    (net (code "102") (name "Vrefdac") (class "Default")
      (node (ref "C93") (pin "2") (pinfunction "2_2") (pintype "passive"))
      (node (ref "C94") (pin "2") (pinfunction "2_2") (pintype "passive"))
      (node (ref "IC15") (pin "2") (pinfunction "VREF_2") (pintype "input"))
      (node (ref "IC17") (pin "6") (pinfunction "OUT_6") (pintype "power_in"))
      (node (ref "IC18") (pin "2") (pinfunction "VREF_2") (pintype "input"))
    )
    (net (code "103") (name "unconnected-(IC6A-OSC_OUT-Pad23)") (class "Default")
      (node (ref "IC6") (pin "23") (pinfunction "OSC_OUT_23") (pintype "output"))
    )
    (net (code "104") (name "unconnected-(IC7A-OUT0-Pad56)") (class "Default")
      (node (ref "IC7") (pin "56") (pinfunction "OUT0_56") (pintype "output"))
    )
    (net (code "105") (name "unconnected-(IC7A-OUT1-Pad53)") (class "Default")
      (node (ref "IC7") (pin "53") (pinfunction "OUT1_53") (pintype "output"))
    )
    (net (code "106") (name "unconnected-(IC7A-OUT2-Pad43)") (class "Default")
      (node (ref "IC7") (pin "43") (pinfunction "OUT2_43") (pintype "output"))
    )
    (net (code "107") (name "unconnected-(IC7A-OUT3-Pad40)") (class "Default")
      (node (ref "IC7") (pin "40") (pinfunction "OUT3_40") (pintype "output"))
    )
    (net (code "108") (name "unconnected-(IC7A-OUT4-Pad25)") (class "Default")
      (node (ref "IC7") (pin "25") (pinfunction "OUT4_25") (pintype "output"))
    )
    (net (code "109") (name "unconnected-(IC7A-REFMON-Pad2)") (class "Default")
      (node (ref "IC7") (pin "2") (pinfunction "REFMON_2") (pintype "output"))
    )
    (net (code "110") (name "unconnected-(IC7A-~{OUT0}-Pad55)") (class "Default")
      (node (ref "IC7") (pin "55") (pinfunction "~{OUT0}_55") (pintype "output"))
    )
    (net (code "111") (name "unconnected-(IC7A-~{OUT1}-Pad52)") (class "Default")
      (node (ref "IC7") (pin "52") (pinfunction "~{OUT1}_52") (pintype "output"))
    )
    (net (code "112") (name "unconnected-(IC7A-~{OUT2}-Pad42)") (class "Default")
      (node (ref "IC7") (pin "42") (pinfunction "~{OUT2}_42") (pintype "output"))
    )
    (net (code "113") (name "unconnected-(IC7A-~{OUT3}-Pad39)") (class "Default")
      (node (ref "IC7") (pin "39") (pinfunction "~{OUT3}_39") (pintype "output"))
    )
    (net (code "114") (name "unconnected-(IC7A-~{OUT4}-Pad26)") (class "Default")
      (node (ref "IC7") (pin "26") (pinfunction "~{OUT4}_26") (pintype "output"))
    )
    (net (code "115") (name "unconnected-(IC7A-~{SYNC}-Pad8)") (class "Default")
      (node (ref "IC7") (pin "8") (pinfunction "~{SYNC}_8") (pintype "input"))
    )
    (net (code "116") (name "unconnected-(IC14A-VBB-Pad4)") (class "Default")
      (node (ref "IC14") (pin "4") (pinfunction "VBB_4") (pintype "passive"))
    )
    (net (code "117") (name "unconnected-(IC17-NC-Pad1)") (class "Default")
      (node (ref "IC17") (pin "1") (pinfunction "NC_1") (pintype "passive"))
    )
    (net (code "118") (name "unconnected-(IC17-NC-Pad7)") (class "Default")
      (node (ref "IC17") (pin "7") (pinfunction "NC_7") (pintype "passive"))
    )
    (net (code "119") (name "unconnected-(IC17-TEMP-Pad3)") (class "Default")
      (node (ref "IC17") (pin "3") (pinfunction "TEMP_3") (pintype "passive"))
    )
    (net (code "120") (name "unconnected-(IC17-TRIM-Pad5)") (class "Default")
      (node (ref "IC17") (pin "5") (pinfunction "TRIM_5") (pintype "passive"))
    )
  )
)
